# GEVCU-5.net
KiCad netlist of a schematic drawn in EAGLE
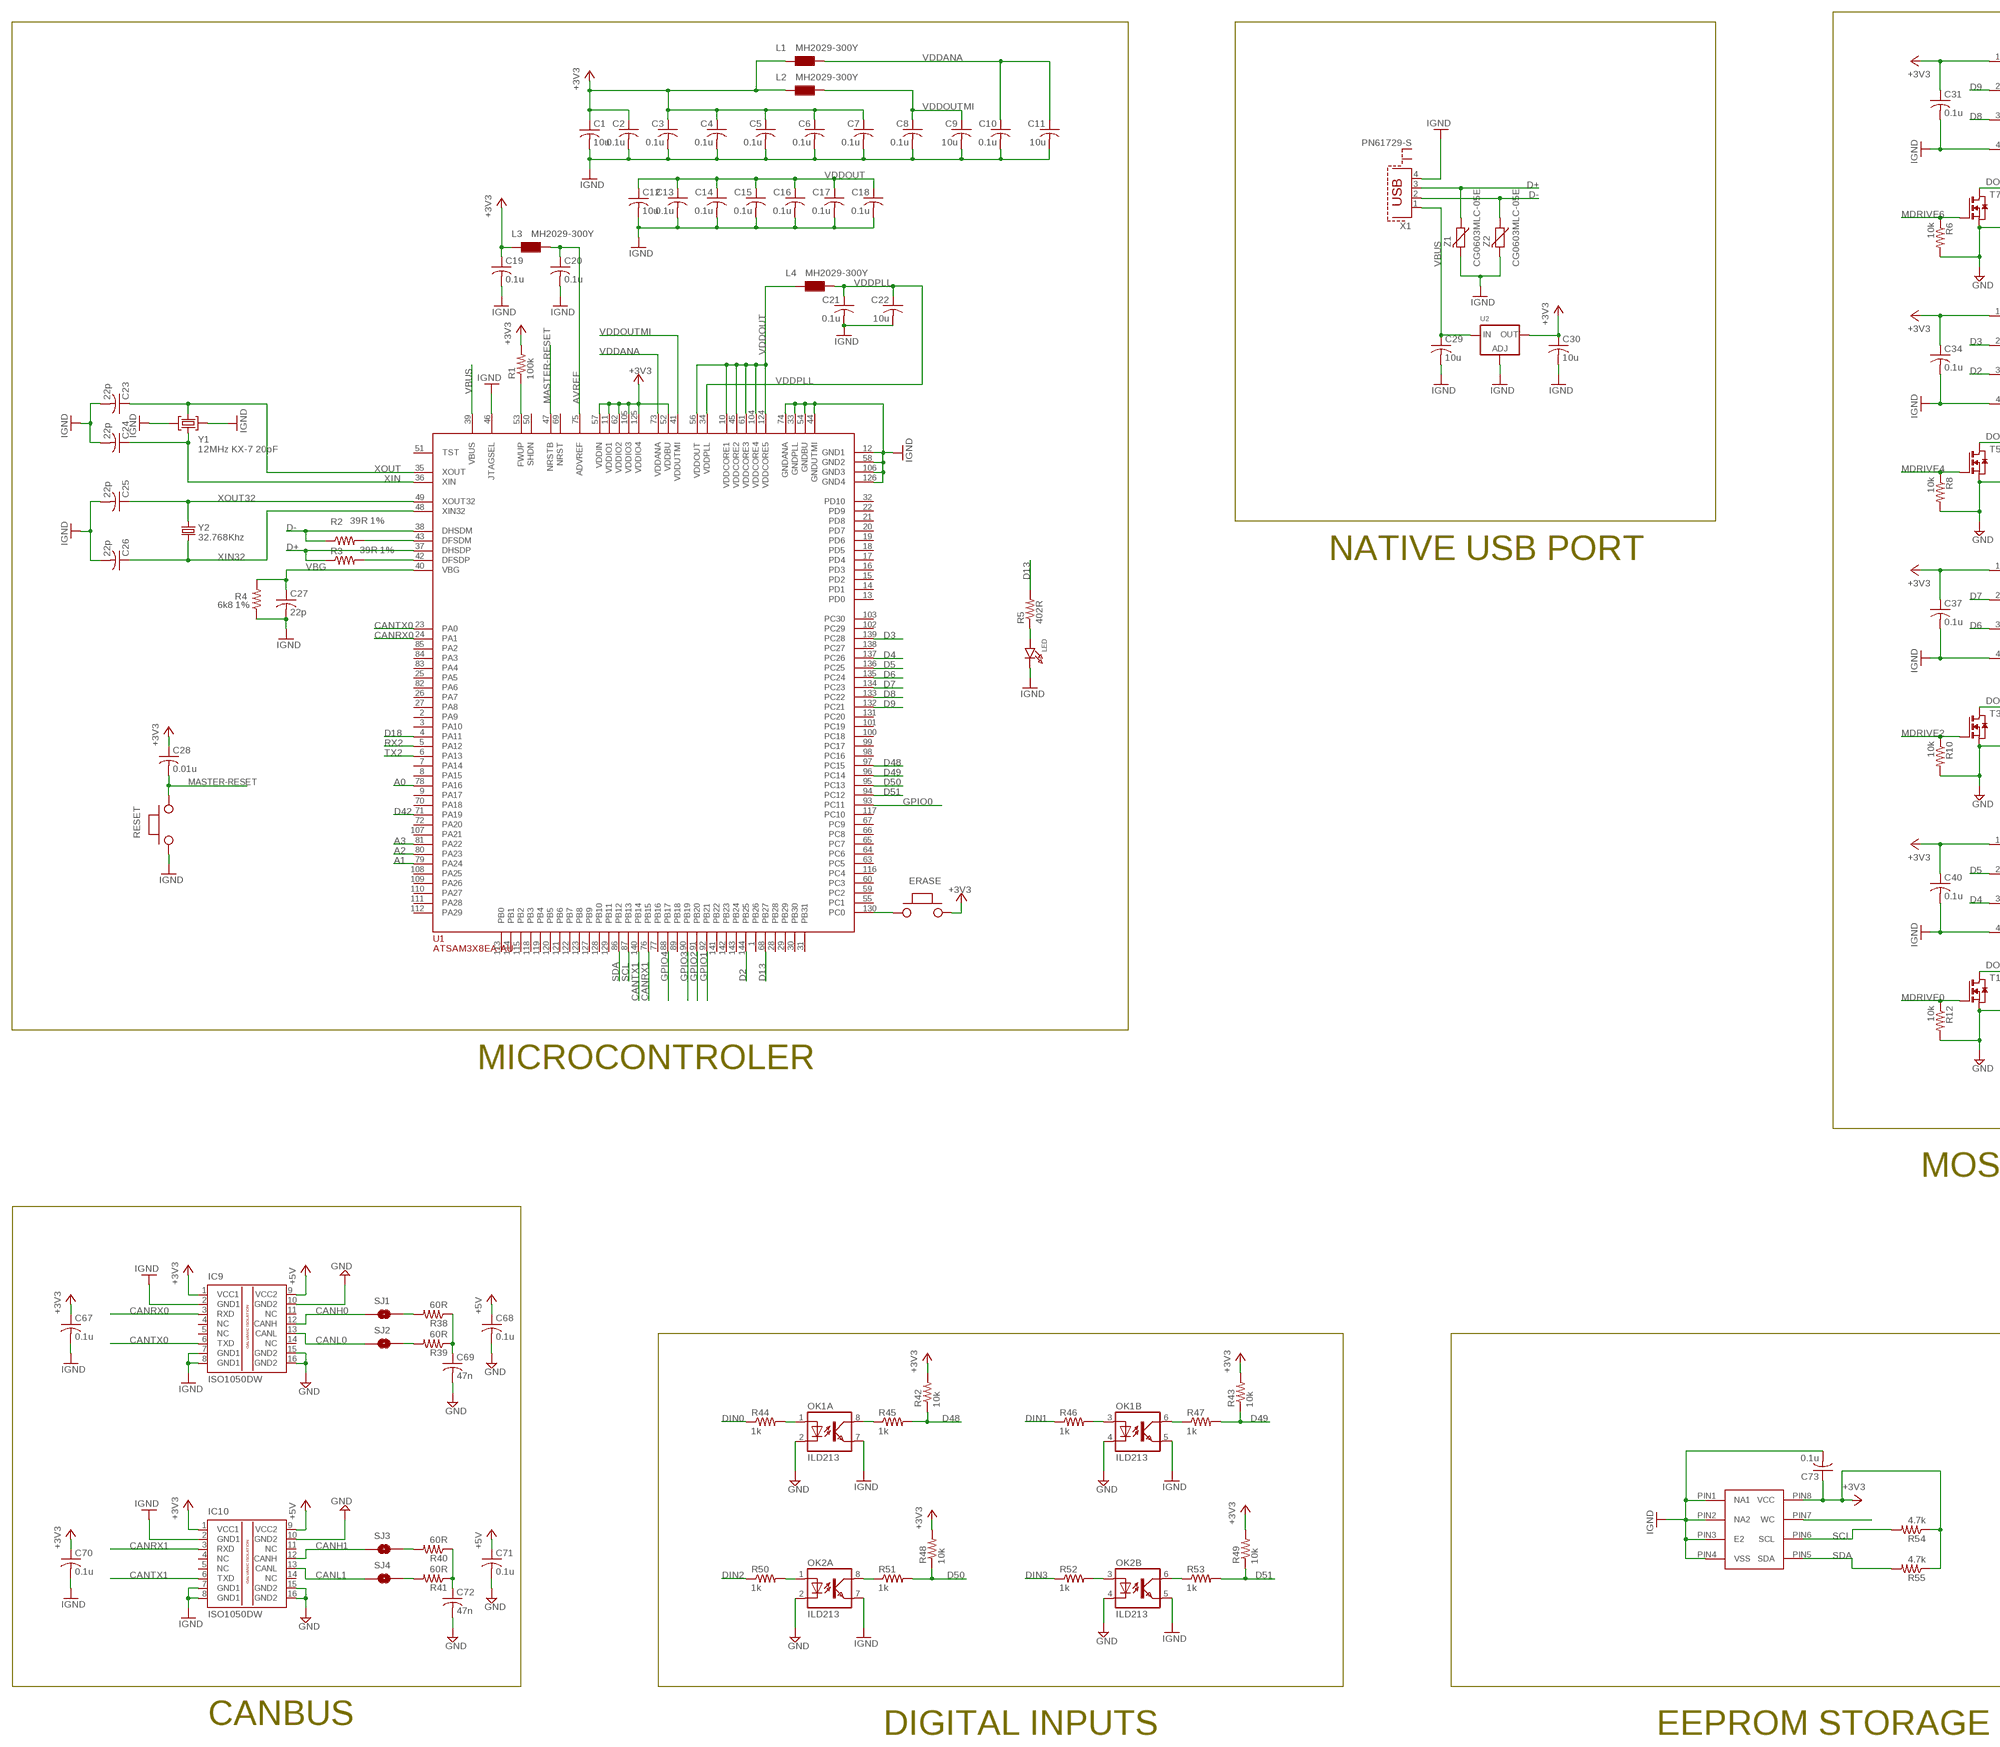
[diagram p0: schematic, sheet 1, part 1 of 2]
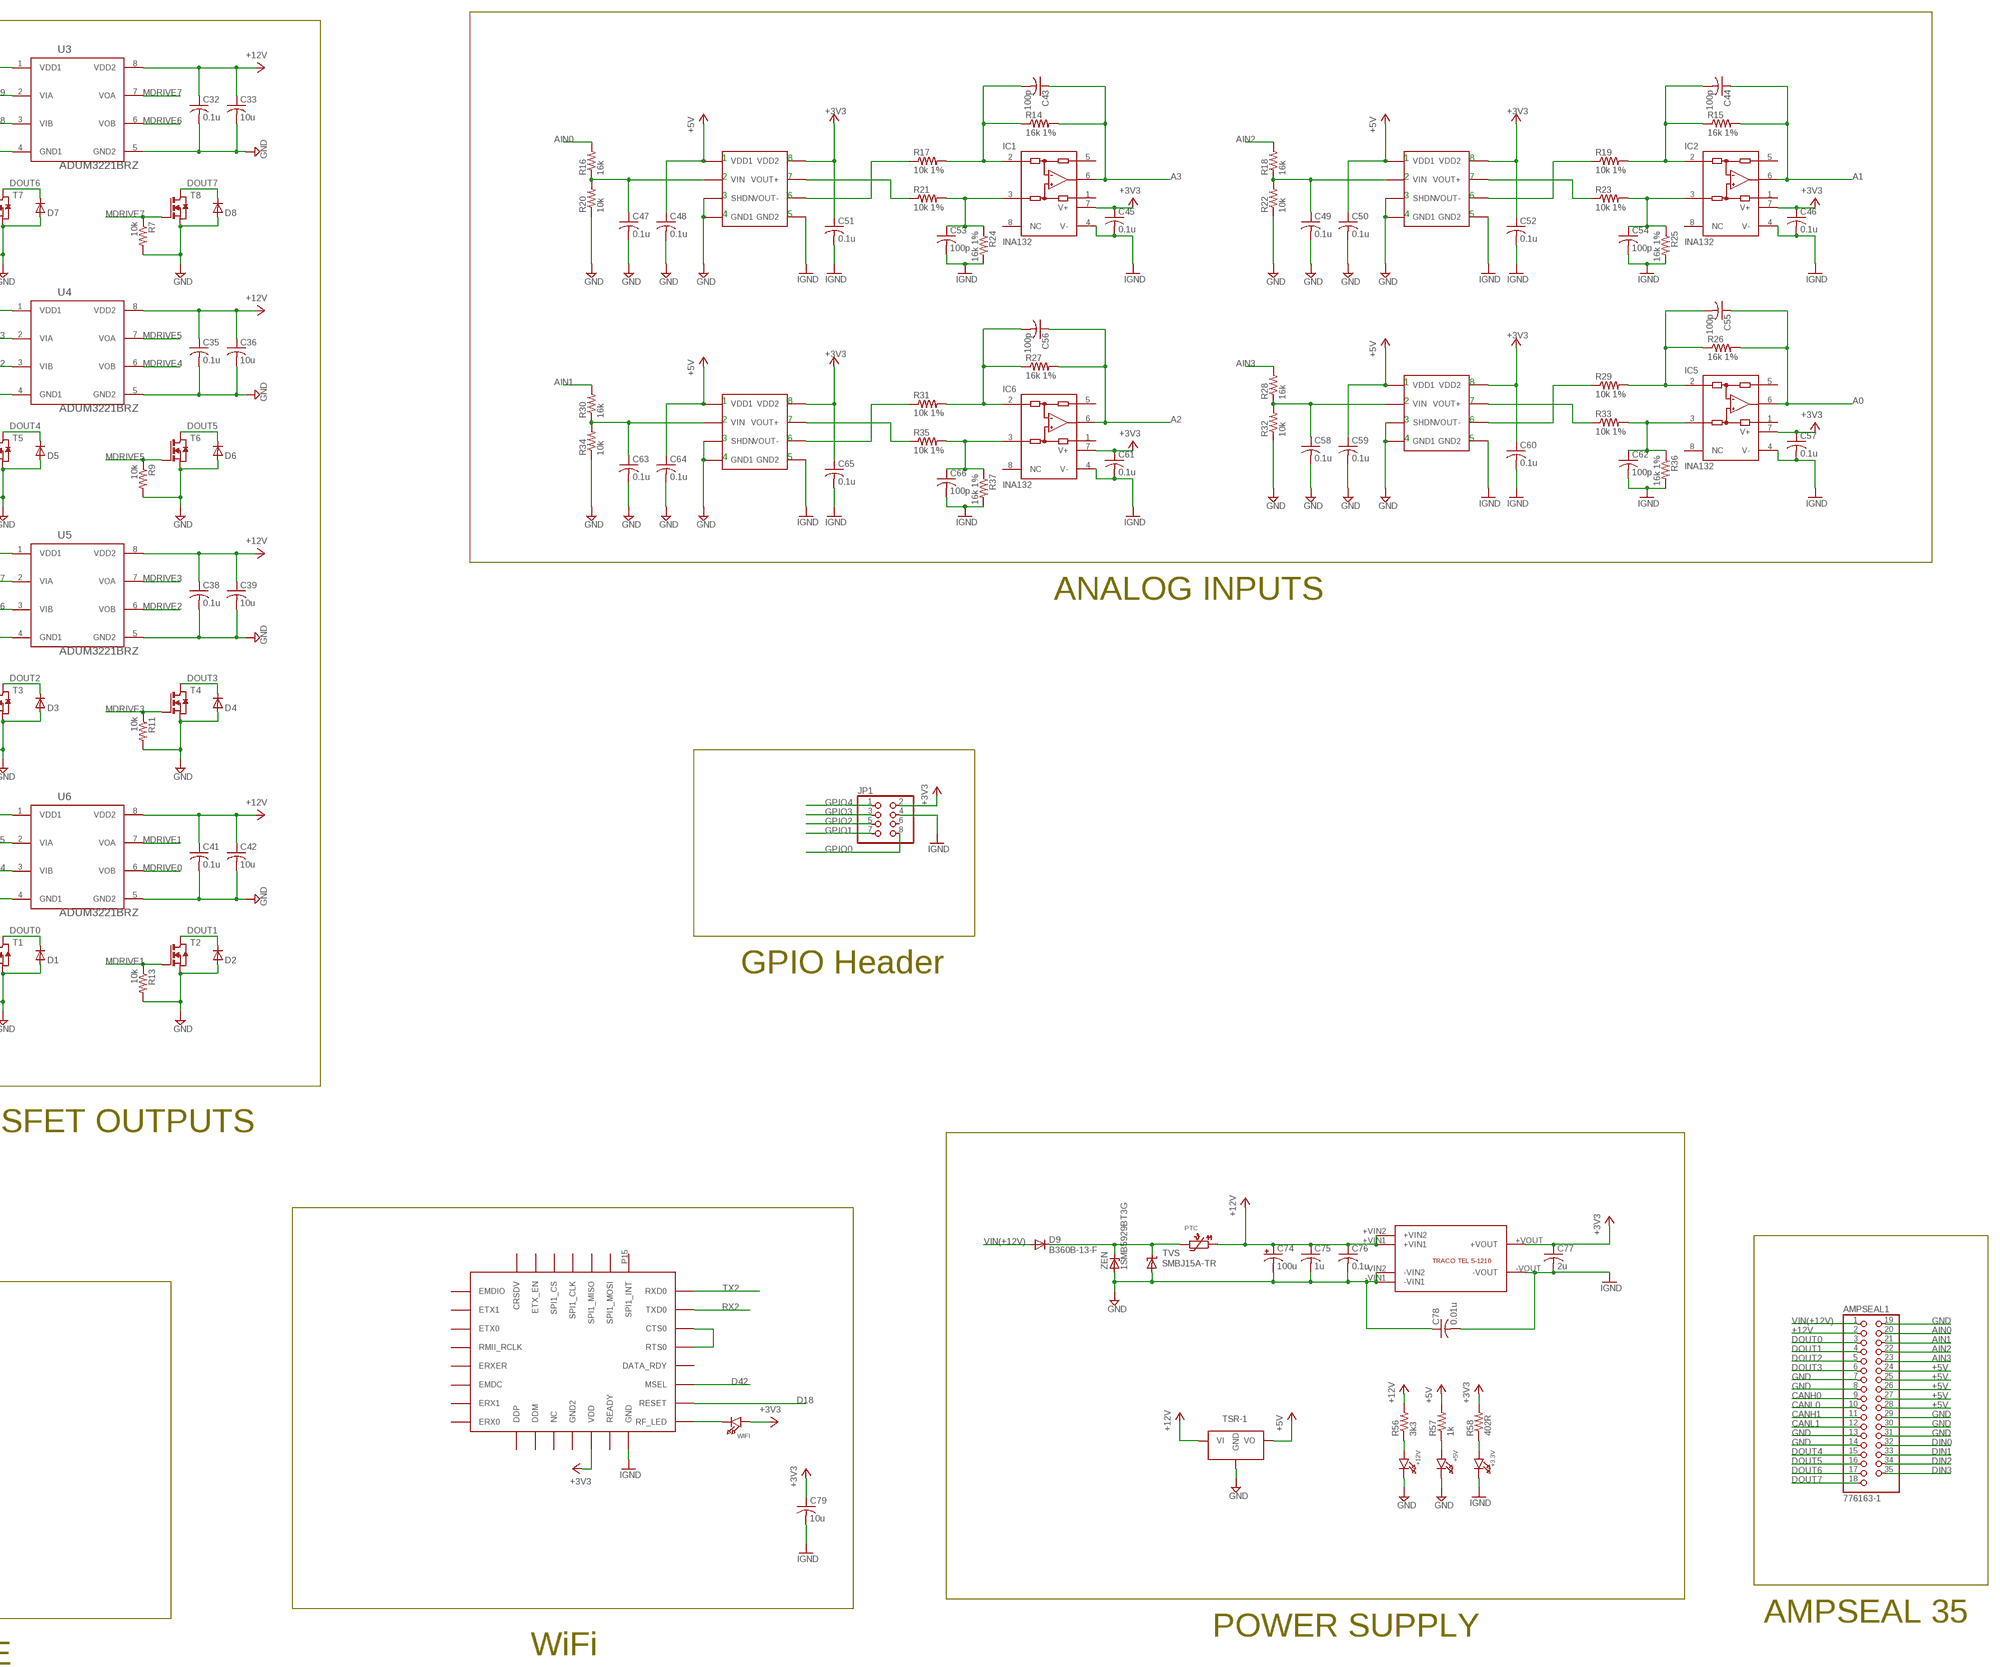
[diagram p1: schematic, sheet 1, part 2 of 2]

(export (version "E")
  (design (tool "Eeschema 10.0.6"))
  (components
    (comp (ref "+3.3V")
      (value "LED0805")
      (footprint "eagle-import:CHIPLED_0805")
      (libsource (lib "eagle-import") (part "LED0805"))
    )
    (comp (ref "+5V")
      (value "LED0805")
      (footprint "eagle-import:CHIPLED_0805")
      (libsource (lib "eagle-import") (part "LED0805"))
    )
    (comp (ref "+12V")
      (value "LED0805")
      (footprint "eagle-import:CHIPLED_0805")
      (libsource (lib "eagle-import") (part "LED0805"))
    )
    (comp (ref "AMPSEAL1")
      (value "776163-1")
      (footprint "eagle-import:AMPSEAL35")
      (libsource (lib "eagle-import") (part "AMPSEAL35"))
    )
    (comp (ref "C1")
      (value "10u")
      (footprint "eagle-import:C0805")
      (libsource (lib "eagle-import") (part "C-USC0805"))
    )
    (comp (ref "C2")
      (value "0.1u")
      (footprint "eagle-import:C0805")
      (libsource (lib "eagle-import") (part "C-USC0805"))
    )
    (comp (ref "C3")
      (value "0.1u")
      (footprint "eagle-import:C0805")
      (libsource (lib "eagle-import") (part "C-USC0805"))
    )
    (comp (ref "C4")
      (value "0.1u")
      (footprint "eagle-import:C0805")
      (libsource (lib "eagle-import") (part "C-USC0805"))
    )
    (comp (ref "C5")
      (value "0.1u")
      (footprint "eagle-import:C0805")
      (libsource (lib "eagle-import") (part "C-USC0805"))
    )
    (comp (ref "C6")
      (value "0.1u")
      (footprint "eagle-import:C0805")
      (libsource (lib "eagle-import") (part "C-USC0805"))
    )
    (comp (ref "C7")
      (value "0.1u")
      (footprint "eagle-import:C0805")
      (libsource (lib "eagle-import") (part "C-USC0805"))
    )
    (comp (ref "C8")
      (value "0.1u")
      (footprint "eagle-import:C0805")
      (libsource (lib "eagle-import") (part "C-USC0805"))
    )
    (comp (ref "C9")
      (value "10u")
      (footprint "eagle-import:C0805")
      (libsource (lib "eagle-import") (part "C-USC0805"))
    )
    (comp (ref "C10")
      (value "0.1u")
      (footprint "eagle-import:C0805")
      (libsource (lib "eagle-import") (part "C-USC0805"))
    )
    (comp (ref "C11")
      (value "10u")
      (footprint "eagle-import:C0805")
      (libsource (lib "eagle-import") (part "C-USC0805"))
    )
    (comp (ref "C12")
      (value "10u")
      (footprint "eagle-import:C0805")
      (libsource (lib "eagle-import") (part "C-USC0805"))
    )
    (comp (ref "C13")
      (value "0.1u")
      (footprint "eagle-import:C0805")
      (libsource (lib "eagle-import") (part "C-USC0805"))
    )
    (comp (ref "C14")
      (value "0.1u")
      (footprint "eagle-import:C0805")
      (libsource (lib "eagle-import") (part "C-USC0805"))
    )
    (comp (ref "C15")
      (value "0.1u")
      (footprint "eagle-import:C0805")
      (libsource (lib "eagle-import") (part "C-USC0805"))
    )
    (comp (ref "C16")
      (value "0.1u")
      (footprint "eagle-import:C0805")
      (libsource (lib "eagle-import") (part "C-USC0805"))
    )
    (comp (ref "C17")
      (value "0.1u")
      (footprint "eagle-import:C0805")
      (libsource (lib "eagle-import") (part "C-USC0805"))
    )
    (comp (ref "C18")
      (value "0.1u")
      (footprint "eagle-import:C0805")
      (libsource (lib "eagle-import") (part "C-USC0805"))
    )
    (comp (ref "C19")
      (value "0.1u")
      (footprint "eagle-import:C0805")
      (libsource (lib "eagle-import") (part "C-USC0805"))
    )
    (comp (ref "C20")
      (value "0.1u")
      (footprint "eagle-import:C0805")
      (libsource (lib "eagle-import") (part "C-USC0805"))
    )
    (comp (ref "C21")
      (value "0.1u")
      (footprint "eagle-import:C0805")
      (libsource (lib "eagle-import") (part "C-USC0805"))
    )
    (comp (ref "C22")
      (value "10u")
      (footprint "eagle-import:C0805")
      (libsource (lib "eagle-import") (part "C-USC0805"))
    )
    (comp (ref "C23")
      (value "22p")
      (footprint "eagle-import:C1206")
      (libsource (lib "eagle-import") (part "C-USC1206"))
    )
    (comp (ref "C24")
      (value "22p")
      (footprint "eagle-import:C1206")
      (libsource (lib "eagle-import") (part "C-USC1206"))
    )
    (comp (ref "C25")
      (value "22p")
      (footprint "eagle-import:C0805")
      (libsource (lib "eagle-import") (part "C-USC0805"))
    )
    (comp (ref "C26")
      (value "22p")
      (footprint "eagle-import:C0805")
      (libsource (lib "eagle-import") (part "C-USC0805"))
    )
    (comp (ref "C27")
      (value "22p")
      (footprint "eagle-import:C0805")
      (libsource (lib "eagle-import") (part "C-USC0805"))
    )
    (comp (ref "C28")
      (value "0.01u")
      (footprint "eagle-import:C0805")
      (libsource (lib "eagle-import") (part "C-USC0805"))
    )
    (comp (ref "C29")
      (value "10u")
      (footprint "eagle-import:C0805")
      (libsource (lib "eagle-import") (part "C-USC0805"))
    )
    (comp (ref "C30")
      (value "10u")
      (footprint "eagle-import:C0805")
      (libsource (lib "eagle-import") (part "C-USC0805"))
    )
    (comp (ref "C31")
      (value "0.1u")
      (footprint "eagle-import:C0805")
      (libsource (lib "eagle-import") (part "C-USC0805"))
    )
    (comp (ref "C32")
      (value "0.1u")
      (footprint "eagle-import:C0805")
      (libsource (lib "eagle-import") (part "C-USC0805"))
    )
    (comp (ref "C33")
      (value "10u")
      (footprint "eagle-import:C0805")
      (libsource (lib "eagle-import") (part "C-USC0805"))
    )
    (comp (ref "C34")
      (value "0.1u")
      (footprint "eagle-import:C0805")
      (libsource (lib "eagle-import") (part "C-USC0805"))
    )
    (comp (ref "C35")
      (value "0.1u")
      (footprint "eagle-import:C0805")
      (libsource (lib "eagle-import") (part "C-USC0805"))
    )
    (comp (ref "C36")
      (value "10u")
      (footprint "eagle-import:C0805")
      (libsource (lib "eagle-import") (part "C-USC0805"))
    )
    (comp (ref "C37")
      (value "0.1u")
      (footprint "eagle-import:C0805")
      (libsource (lib "eagle-import") (part "C-USC0805"))
    )
    (comp (ref "C38")
      (value "0.1u")
      (footprint "eagle-import:C0805")
      (libsource (lib "eagle-import") (part "C-USC0805"))
    )
    (comp (ref "C39")
      (value "10u")
      (footprint "eagle-import:C0805")
      (libsource (lib "eagle-import") (part "C-USC0805"))
    )
    (comp (ref "C40")
      (value "0.1u")
      (footprint "eagle-import:C0805")
      (libsource (lib "eagle-import") (part "C-USC0805"))
    )
    (comp (ref "C41")
      (value "0.1u")
      (footprint "eagle-import:C0805")
      (libsource (lib "eagle-import") (part "C-USC0805"))
    )
    (comp (ref "C42")
      (value "10u")
      (footprint "eagle-import:C0805")
      (libsource (lib "eagle-import") (part "C-USC0805"))
    )
    (comp (ref "C43")
      (value "100p")
      (footprint "eagle-import:C0805")
      (libsource (lib "eagle-import") (part "C-USC0805"))
    )
    (comp (ref "C44")
      (value "100p")
      (footprint "eagle-import:C0805")
      (libsource (lib "eagle-import") (part "C-USC0805"))
    )
    (comp (ref "C45")
      (value "0.1u")
      (footprint "eagle-import:C0805")
      (libsource (lib "eagle-import") (part "C-USC0805"))
    )
    (comp (ref "C46")
      (value "0.1u")
      (footprint "eagle-import:C0805")
      (libsource (lib "eagle-import") (part "C-USC0805"))
    )
    (comp (ref "C47")
      (value "0.1u")
      (footprint "eagle-import:C0805")
      (libsource (lib "eagle-import") (part "C-USC0805"))
    )
    (comp (ref "C48")
      (value "0.1u")
      (footprint "eagle-import:C1206")
      (libsource (lib "eagle-import") (part "C-USC1206"))
    )
    (comp (ref "C49")
      (value "0.1u")
      (footprint "eagle-import:C0805")
      (libsource (lib "eagle-import") (part "C-USC0805"))
    )
    (comp (ref "C50")
      (value "0.1u")
      (footprint "eagle-import:C1206")
      (libsource (lib "eagle-import") (part "C-USC1206"))
    )
    (comp (ref "C51")
      (value "0.1u")
      (footprint "eagle-import:C0805")
      (libsource (lib "eagle-import") (part "C-USC0805"))
    )
    (comp (ref "C52")
      (value "0.1u")
      (footprint "eagle-import:C0805")
      (libsource (lib "eagle-import") (part "C-USC0805"))
    )
    (comp (ref "C53")
      (value "100p")
      (footprint "eagle-import:C0805")
      (libsource (lib "eagle-import") (part "C-USC0805"))
    )
    (comp (ref "C54")
      (value "100p")
      (footprint "eagle-import:C0805")
      (libsource (lib "eagle-import") (part "C-USC0805"))
    )
    (comp (ref "C55")
      (value "100p")
      (footprint "eagle-import:C0805")
      (libsource (lib "eagle-import") (part "C-USC0805"))
    )
    (comp (ref "C56")
      (value "100p")
      (footprint "eagle-import:C0805")
      (libsource (lib "eagle-import") (part "C-USC0805"))
    )
    (comp (ref "C57")
      (value "0.1u")
      (footprint "eagle-import:C0805")
      (libsource (lib "eagle-import") (part "C-USC0805"))
    )
    (comp (ref "C58")
      (value "0.1u")
      (footprint "eagle-import:C0805")
      (libsource (lib "eagle-import") (part "C-USC0805"))
    )
    (comp (ref "C59")
      (value "0.1u")
      (footprint "eagle-import:C1206")
      (libsource (lib "eagle-import") (part "C-USC1206"))
    )
    (comp (ref "C60")
      (value "0.1u")
      (footprint "eagle-import:C0805")
      (libsource (lib "eagle-import") (part "C-USC0805"))
    )
    (comp (ref "C61")
      (value "0.1u")
      (footprint "eagle-import:C0805")
      (libsource (lib "eagle-import") (part "C-USC0805"))
    )
    (comp (ref "C62")
      (value "100p")
      (footprint "eagle-import:C0805")
      (libsource (lib "eagle-import") (part "C-USC0805"))
    )
    (comp (ref "C63")
      (value "0.1u")
      (footprint "eagle-import:C0805")
      (libsource (lib "eagle-import") (part "C-USC0805"))
    )
    (comp (ref "C64")
      (value "0.1u")
      (footprint "eagle-import:C1206")
      (libsource (lib "eagle-import") (part "C-USC1206"))
    )
    (comp (ref "C65")
      (value "0.1u")
      (footprint "eagle-import:C0805")
      (libsource (lib "eagle-import") (part "C-USC0805"))
    )
    (comp (ref "C66")
      (value "100p")
      (footprint "eagle-import:C0805")
      (libsource (lib "eagle-import") (part "C-USC0805"))
    )
    (comp (ref "C67")
      (value "0.1u")
      (footprint "eagle-import:C0805")
      (libsource (lib "eagle-import") (part "C-USC0805"))
    )
    (comp (ref "C68")
      (value "0.1u")
      (footprint "eagle-import:C0805")
      (libsource (lib "eagle-import") (part "C-USC0805"))
    )
    (comp (ref "C69")
      (value "47n")
      (footprint "eagle-import:C0805")
      (libsource (lib "eagle-import") (part "C-USC0805"))
    )
    (comp (ref "C70")
      (value "0.1u")
      (footprint "eagle-import:C0805")
      (libsource (lib "eagle-import") (part "C-USC0805"))
    )
    (comp (ref "C71")
      (value "0.1u")
      (footprint "eagle-import:C0805")
      (libsource (lib "eagle-import") (part "C-USC0805"))
    )
    (comp (ref "C72")
      (value "47n")
      (footprint "eagle-import:C0805")
      (libsource (lib "eagle-import") (part "C-USC0805"))
    )
    (comp (ref "C73")
      (value "0.1u")
      (footprint "eagle-import:C0805")
      (libsource (lib "eagle-import") (part "C-USC0805"))
    )
    (comp (ref "C74")
      (value "100u")
      (footprint "eagle-import:E2,5-6")
      (libsource (lib "eagle-import") (part "CPOL-USE2.5-6"))
    )
    (comp (ref "C75")
      (value "1u")
      (footprint "eagle-import:C0805")
      (libsource (lib "eagle-import") (part "C-USC0805"))
    )
    (comp (ref "C76")
      (value "0.1u")
      (footprint "eagle-import:C0805")
      (libsource (lib "eagle-import") (part "C-USC0805"))
    )
    (comp (ref "C77")
      (value "2u")
      (footprint "eagle-import:C0805")
      (libsource (lib "eagle-import") (part "C-USC0805"))
    )
    (comp (ref "C78")
      (value "0.01u")
      (footprint "eagle-import:C1812")
      (libsource (lib "eagle-import") (part "C-USC1812"))
    )
    (comp (ref "C79")
      (value "10u")
      (footprint "eagle-import:C0805")
      (libsource (lib "eagle-import") (part "C-USC0805"))
    )
    (comp (ref "D1")
      (value "MBR0520LT")
      (footprint "eagle-import:SOD123")
      (libsource (lib "eagle-import") (part "MBR0520LT"))
    )
    (comp (ref "D2")
      (value "MBR0520LT")
      (footprint "eagle-import:SOD123")
      (libsource (lib "eagle-import") (part "MBR0520LT"))
    )
    (comp (ref "D3")
      (value "MBR0520LT")
      (footprint "eagle-import:SOD123")
      (libsource (lib "eagle-import") (part "MBR0520LT"))
    )
    (comp (ref "D4")
      (value "MBR0520LT")
      (footprint "eagle-import:SOD123")
      (libsource (lib "eagle-import") (part "MBR0520LT"))
    )
    (comp (ref "D5")
      (value "MBR0520LT")
      (footprint "eagle-import:SOD123")
      (libsource (lib "eagle-import") (part "MBR0520LT"))
    )
    (comp (ref "D6")
      (value "MBR0520LT")
      (footprint "eagle-import:SOD123")
      (libsource (lib "eagle-import") (part "MBR0520LT"))
    )
    (comp (ref "D7")
      (value "MBR0520LT")
      (footprint "eagle-import:SOD123")
      (libsource (lib "eagle-import") (part "MBR0520LT"))
    )
    (comp (ref "D8")
      (value "MBR0520LT")
      (footprint "eagle-import:SOD123")
      (libsource (lib "eagle-import") (part "MBR0520LT"))
    )
    (comp (ref "D9")
      (value "B360B-13-F")
      (footprint "eagle-import:SMB")
      (libsource (lib "eagle-import") (part "DIODE-SMB"))
    )
    (comp (ref "ERASE")
      (value "PUCHBUTTON")
      (footprint "eagle-import:PUCHBUTTON")
      (libsource (lib "eagle-import") (part "PUCHBUTTON"))
    )
    (comp (ref "IC1")
      (value "INA132")
      (footprint "eagle-import:SO08")
      (fields (field (name "MF") "TEXAS INSTRUMENTS") (field (name "MPN") "INA105KU"))
      (libsource (lib "eagle-import") (part "INA105U"))
    )
    (comp (ref "IC2")
      (value "INA132")
      (footprint "eagle-import:SO08")
      (fields (field (name "MF") "TEXAS INSTRUMENTS") (field (name "MPN") "INA105KU"))
      (libsource (lib "eagle-import") (part "INA105U"))
    )
    (comp (ref "IC3")
      (value "CK_CUSTOM_ACPL-C87A-000E")
      (footprint "eagle-import:CK_CUSTOM_SO8-WIDE")
      (libsource (lib "eagle-import") (part "CK_CUSTOM_ACPL-C87A-000E"))
    )
    (comp (ref "IC4")
      (value "CK_CUSTOM_ACPL-C87A-000E")
      (footprint "eagle-import:CK_CUSTOM_SO8-WIDE")
      (libsource (lib "eagle-import") (part "CK_CUSTOM_ACPL-C87A-000E"))
    )
    (comp (ref "IC5")
      (value "INA132")
      (footprint "eagle-import:SO08")
      (fields (field (name "MF") "TEXAS INSTRUMENTS") (field (name "MPN") "INA105KU"))
      (libsource (lib "eagle-import") (part "INA105U"))
    )
    (comp (ref "IC6")
      (value "INA132")
      (footprint "eagle-import:SO08")
      (fields (field (name "MF") "TEXAS INSTRUMENTS") (field (name "MPN") "INA105KU"))
      (libsource (lib "eagle-import") (part "INA105U"))
    )
    (comp (ref "IC7")
      (value "CK_CUSTOM_ACPL-C87A-000E")
      (footprint "eagle-import:CK_CUSTOM_SO8-WIDE")
      (libsource (lib "eagle-import") (part "CK_CUSTOM_ACPL-C87A-000E"))
    )
    (comp (ref "IC8")
      (value "CK_CUSTOM_ACPL-C87A-000E")
      (footprint "eagle-import:CK_CUSTOM_SO8-WIDE")
      (libsource (lib "eagle-import") (part "CK_CUSTOM_ACPL-C87A-000E"))
    )
    (comp (ref "IC9")
      (value "ISO1050DW")
      (footprint "eagle-import:DUB-R-PDSO-G8")
      (libsource (lib "eagle-import") (part "ISO1050DUB"))
    )
    (comp (ref "IC10")
      (value "ISO1050DW")
      (footprint "eagle-import:DUB-R-PDSO-G8")
      (libsource (lib "eagle-import") (part "ISO1050DUB"))
    )
    (comp (ref "JP1")
      (value "PINHD-2X4")
      (footprint "eagle-import:2X04")
      (libsource (lib "eagle-import") (part "PINHD-2X4"))
    )
    (comp (ref "L1")
      (value "MH2029-300Y")
      (footprint "eagle-import:0805")
      (libsource (lib "eagle-import") (part "WE-CBF_0805"))
    )
    (comp (ref "L2")
      (value "MH2029-300Y")
      (footprint "eagle-import:0805")
      (libsource (lib "eagle-import") (part "WE-CBF_0805"))
    )
    (comp (ref "L3")
      (value "MH2029-300Y")
      (footprint "eagle-import:0805")
      (libsource (lib "eagle-import") (part "WE-CBF_0805"))
    )
    (comp (ref "L4")
      (value "MH2029-300Y")
      (footprint "eagle-import:0805")
      (libsource (lib "eagle-import") (part "WE-CBF_0805"))
    )
    (comp (ref "LED")
      (value "LED0805")
      (footprint "eagle-import:CHIPLED_0805")
      (libsource (lib "eagle-import") (part "LED0805"))
    )
    (comp (ref "OK1")
      (value "ILD213")
      (footprint "eagle-import:SOIC08")
      (fields (field (name "MF") "VISHAY/TELEFUNKEN") (field (name "MPN") "ILD213T"))
      (libsource (lib "eagle-import") (part "ILD213"))
    )
    (comp (ref "OK2")
      (value "ILD213")
      (footprint "eagle-import:SOIC08")
      (fields (field (name "MF") "VISHAY/TELEFUNKEN") (field (name "MPN") "ILD213T"))
      (libsource (lib "eagle-import") (part "ILD213"))
    )
    (comp (ref "PTC")
      (value "PTC1812")
      (footprint "eagle-import:PTC1812")
      (libsource (lib "eagle-import") (part "PTC1812"))
    )
    (comp (ref "R1")
      (value "100k")
      (footprint "eagle-import:R0805")
      (libsource (lib "eagle-import") (part "R-US_R0805"))
    )
    (comp (ref "R2")
      (value "39R 1%")
      (footprint "eagle-import:R0805")
      (libsource (lib "eagle-import") (part "R-US_R0805"))
    )
    (comp (ref "R3")
      (value "39R 1%")
      (footprint "eagle-import:R0805")
      (libsource (lib "eagle-import") (part "R-US_R0805"))
    )
    (comp (ref "R4")
      (value "6k8 1%")
      (footprint "eagle-import:R0805")
      (libsource (lib "eagle-import") (part "R-US_R0805"))
    )
    (comp (ref "R5")
      (value "402R")
      (footprint "eagle-import:R0805")
      (libsource (lib "eagle-import") (part "R-US_R0805"))
    )
    (comp (ref "R6")
      (value "10k")
      (footprint "eagle-import:R0805")
      (libsource (lib "eagle-import") (part "R-US_R0805"))
    )
    (comp (ref "R7")
      (value "10k")
      (footprint "eagle-import:R0805")
      (libsource (lib "eagle-import") (part "R-US_R0805"))
    )
    (comp (ref "R8")
      (value "10k")
      (footprint "eagle-import:R0805")
      (libsource (lib "eagle-import") (part "R-US_R0805"))
    )
    (comp (ref "R9")
      (value "10k")
      (footprint "eagle-import:R0805")
      (libsource (lib "eagle-import") (part "R-US_R0805"))
    )
    (comp (ref "R10")
      (value "10k")
      (footprint "eagle-import:R0805")
      (libsource (lib "eagle-import") (part "R-US_R0805"))
    )
    (comp (ref "R11")
      (value "10k")
      (footprint "eagle-import:R0805")
      (libsource (lib "eagle-import") (part "R-US_R0805"))
    )
    (comp (ref "R12")
      (value "10k")
      (footprint "eagle-import:R0805")
      (libsource (lib "eagle-import") (part "R-US_R0805"))
    )
    (comp (ref "R13")
      (value "10k")
      (footprint "eagle-import:R0805")
      (libsource (lib "eagle-import") (part "R-US_R0805"))
    )
    (comp (ref "R14")
      (value "16k 1%")
      (footprint "eagle-import:R0805")
      (libsource (lib "eagle-import") (part "R-US_R0805"))
    )
    (comp (ref "R15")
      (value "16k 1%")
      (footprint "eagle-import:R0805")
      (libsource (lib "eagle-import") (part "R-US_R0805"))
    )
    (comp (ref "R16")
      (value "16k")
      (footprint "eagle-import:R0805")
      (libsource (lib "eagle-import") (part "R-US_R0805"))
    )
    (comp (ref "R17")
      (value "10k 1%")
      (footprint "eagle-import:R0805")
      (libsource (lib "eagle-import") (part "R-US_R0805"))
    )
    (comp (ref "R18")
      (value "16k")
      (footprint "eagle-import:R0805")
      (libsource (lib "eagle-import") (part "R-US_R0805"))
    )
    (comp (ref "R19")
      (value "10k 1%")
      (footprint "eagle-import:R0805")
      (libsource (lib "eagle-import") (part "R-US_R0805"))
    )
    (comp (ref "R20")
      (value "10k")
      (footprint "eagle-import:R0805")
      (libsource (lib "eagle-import") (part "R-US_R0805"))
    )
    (comp (ref "R21")
      (value "10k 1%")
      (footprint "eagle-import:R0805")
      (libsource (lib "eagle-import") (part "R-US_R0805"))
    )
    (comp (ref "R22")
      (value "10k")
      (footprint "eagle-import:R0805")
      (libsource (lib "eagle-import") (part "R-US_R0805"))
    )
    (comp (ref "R23")
      (value "10k 1%")
      (footprint "eagle-import:R0805")
      (libsource (lib "eagle-import") (part "R-US_R0805"))
    )
    (comp (ref "R24")
      (value "16k 1%")
      (footprint "eagle-import:R0805")
      (libsource (lib "eagle-import") (part "R-US_R0805"))
    )
    (comp (ref "R25")
      (value "16k 1%")
      (footprint "eagle-import:R0805")
      (libsource (lib "eagle-import") (part "R-US_R0805"))
    )
    (comp (ref "R26")
      (value "16k 1%")
      (footprint "eagle-import:R0805")
      (libsource (lib "eagle-import") (part "R-US_R0805"))
    )
    (comp (ref "R27")
      (value "16k 1%")
      (footprint "eagle-import:R0805")
      (libsource (lib "eagle-import") (part "R-US_R0805"))
    )
    (comp (ref "R28")
      (value "16k")
      (footprint "eagle-import:R0805")
      (libsource (lib "eagle-import") (part "R-US_R0805"))
    )
    (comp (ref "R29")
      (value "10k 1%")
      (footprint "eagle-import:R0805")
      (libsource (lib "eagle-import") (part "R-US_R0805"))
    )
    (comp (ref "R30")
      (value "16k")
      (footprint "eagle-import:R0805")
      (libsource (lib "eagle-import") (part "R-US_R0805"))
    )
    (comp (ref "R31")
      (value "10k 1%")
      (footprint "eagle-import:R0805")
      (libsource (lib "eagle-import") (part "R-US_R0805"))
    )
    (comp (ref "R32")
      (value "10k")
      (footprint "eagle-import:R0805")
      (libsource (lib "eagle-import") (part "R-US_R0805"))
    )
    (comp (ref "R33")
      (value "10k 1%")
      (footprint "eagle-import:R0805")
      (libsource (lib "eagle-import") (part "R-US_R0805"))
    )
    (comp (ref "R34")
      (value "10k")
      (footprint "eagle-import:R0805")
      (libsource (lib "eagle-import") (part "R-US_R0805"))
    )
    (comp (ref "R35")
      (value "10k 1%")
      (footprint "eagle-import:R0805")
      (libsource (lib "eagle-import") (part "R-US_R0805"))
    )
    (comp (ref "R36")
      (value "16k 1%")
      (footprint "eagle-import:R0805")
      (libsource (lib "eagle-import") (part "R-US_R0805"))
    )
    (comp (ref "R37")
      (value "16k 1%")
      (footprint "eagle-import:R0805")
      (libsource (lib "eagle-import") (part "R-US_R0805"))
    )
    (comp (ref "R38")
      (value "60R")
      (footprint "eagle-import:R0805")
      (libsource (lib "eagle-import") (part "R-US_R0805"))
    )
    (comp (ref "R39")
      (value "60R")
      (footprint "eagle-import:R0805")
      (libsource (lib "eagle-import") (part "R-US_R0805"))
    )
    (comp (ref "R40")
      (value "60R")
      (footprint "eagle-import:R0805")
      (libsource (lib "eagle-import") (part "R-US_R0805"))
    )
    (comp (ref "R41")
      (value "60R")
      (footprint "eagle-import:R0805")
      (libsource (lib "eagle-import") (part "R-US_R0805"))
    )
    (comp (ref "R42")
      (value "10k")
      (footprint "eagle-import:R0805")
      (libsource (lib "eagle-import") (part "R-US_R0805"))
    )
    (comp (ref "R43")
      (value "10k")
      (footprint "eagle-import:R0805")
      (libsource (lib "eagle-import") (part "R-US_R0805"))
    )
    (comp (ref "R44")
      (value "1k")
      (footprint "eagle-import:R0805")
      (libsource (lib "eagle-import") (part "R-US_R0805"))
    )
    (comp (ref "R45")
      (value "1k")
      (footprint "eagle-import:R0805")
      (libsource (lib "eagle-import") (part "R-US_R0805"))
    )
    (comp (ref "R46")
      (value "1k")
      (footprint "eagle-import:R0805")
      (libsource (lib "eagle-import") (part "R-US_R0805"))
    )
    (comp (ref "R47")
      (value "1k")
      (footprint "eagle-import:R0805")
      (libsource (lib "eagle-import") (part "R-US_R0805"))
    )
    (comp (ref "R48")
      (value "10k")
      (footprint "eagle-import:R0805")
      (libsource (lib "eagle-import") (part "R-US_R0805"))
    )
    (comp (ref "R49")
      (value "10k")
      (footprint "eagle-import:R0805")
      (libsource (lib "eagle-import") (part "R-US_R0805"))
    )
    (comp (ref "R50")
      (value "1k")
      (footprint "eagle-import:R0805")
      (libsource (lib "eagle-import") (part "R-US_R0805"))
    )
    (comp (ref "R51")
      (value "1k")
      (footprint "eagle-import:R0805")
      (libsource (lib "eagle-import") (part "R-US_R0805"))
    )
    (comp (ref "R52")
      (value "1k")
      (footprint "eagle-import:R0805")
      (libsource (lib "eagle-import") (part "R-US_R0805"))
    )
    (comp (ref "R53")
      (value "1k")
      (footprint "eagle-import:R0805")
      (libsource (lib "eagle-import") (part "R-US_R0805"))
    )
    (comp (ref "R54")
      (value "4.7k")
      (footprint "eagle-import:R0805")
      (libsource (lib "eagle-import") (part "R-US_R0805"))
    )
    (comp (ref "R55")
      (value "4.7k")
      (footprint "eagle-import:R0805")
      (libsource (lib "eagle-import") (part "R-US_R0805"))
    )
    (comp (ref "R56")
      (value "3k3")
      (footprint "eagle-import:R0805")
      (libsource (lib "eagle-import") (part "R-US_R0805"))
    )
    (comp (ref "R57")
      (value "1k")
      (footprint "eagle-import:R0805")
      (libsource (lib "eagle-import") (part "R-US_R0805"))
    )
    (comp (ref "R58")
      (value "402R")
      (footprint "eagle-import:R0805")
      (libsource (lib "eagle-import") (part "R-US_R0805"))
    )
    (comp (ref "RESET")
      (value "PUCHBUTTON")
      (footprint "eagle-import:PUCHBUTTON")
      (libsource (lib "eagle-import") (part "PUCHBUTTON"))
    )
    (comp (ref "SJ1")
      (value "SOLDERJUMPERNO")
      (footprint "eagle-import:SJ_2S-NO")
      (libsource (lib "eagle-import") (part "SOLDERJUMPERNO"))
    )
    (comp (ref "SJ2")
      (value "SOLDERJUMPERNO")
      (footprint "eagle-import:SJ_2S-NO")
      (libsource (lib "eagle-import") (part "SOLDERJUMPERNO"))
    )
    (comp (ref "SJ3")
      (value "SOLDERJUMPERNO")
      (footprint "eagle-import:SJ_2S-NO")
      (libsource (lib "eagle-import") (part "SOLDERJUMPERNO"))
    )
    (comp (ref "SJ4")
      (value "SOLDERJUMPERNO")
      (footprint "eagle-import:SJ_2S-NO")
      (libsource (lib "eagle-import") (part "SOLDERJUMPERNO"))
    )
    (comp (ref "T1")
      (value "NMOSSOT223")
      (footprint "eagle-import:SOT223")
      (libsource (lib "eagle-import") (part "NMOSSOT223"))
    )
    (comp (ref "T2")
      (value "NMOSSOT223")
      (footprint "eagle-import:SOT223")
      (libsource (lib "eagle-import") (part "NMOSSOT223"))
    )
    (comp (ref "T3")
      (value "NMOSSOT223")
      (footprint "eagle-import:SOT223")
      (libsource (lib "eagle-import") (part "NMOSSOT223"))
    )
    (comp (ref "T4")
      (value "NMOSSOT223")
      (footprint "eagle-import:SOT223")
      (libsource (lib "eagle-import") (part "NMOSSOT223"))
    )
    (comp (ref "T5")
      (value "NMOSSOT223")
      (footprint "eagle-import:SOT223")
      (libsource (lib "eagle-import") (part "NMOSSOT223"))
    )
    (comp (ref "T6")
      (value "NMOSSOT223")
      (footprint "eagle-import:SOT223")
      (libsource (lib "eagle-import") (part "NMOSSOT223"))
    )
    (comp (ref "T7")
      (value "NMOSSOT223")
      (footprint "eagle-import:SOT223")
      (libsource (lib "eagle-import") (part "NMOSSOT223"))
    )
    (comp (ref "T8")
      (value "NMOSSOT223")
      (footprint "eagle-import:SOT223")
      (libsource (lib "eagle-import") (part "NMOSSOT223"))
    )
    (comp (ref "TVS")
      (value "SMBJ15A-TR")
      (footprint "eagle-import:SMBJ")
      (libsource (lib "eagle-import") (part "SUPPRESSOR-SMBJ"))
    )
    (comp (ref "U$1")
      (value "NANOREACH")
      (footprint "eagle-import:NANOREACH")
      (libsource (lib "eagle-import") (part "NANOREACH"))
    )
    (comp (ref "U1")
      (value "ATSAM3X8EA-AU")
      (footprint "eagle-import:LQFP144")
      (libsource (lib "eagle-import") (part "ATSAM3X/AAU"))
    )
    (comp (ref "U2")
      (value "LM1117SOT223-WAVE")
      (footprint "eagle-import:SOT223-W")
      (libsource (lib "eagle-import") (part "LM1117SOT223-WAVE"))
    )
    (comp (ref "U3")
      (value "ADUM3221BRZ")
      (footprint "eagle-import:SOIC127P600X175-8N")
      (libsource (lib "eagle-import") (part "ADUM3221BRZ"))
    )
    (comp (ref "U4")
      (value "ADUM3221BRZ")
      (footprint "eagle-import:SOIC127P600X175-8N")
      (libsource (lib "eagle-import") (part "ADUM3221BRZ"))
    )
    (comp (ref "U5")
      (value "ADUM3221BRZ")
      (footprint "eagle-import:SOIC127P600X175-8N")
      (libsource (lib "eagle-import") (part "ADUM3221BRZ"))
    )
    (comp (ref "U6")
      (value "ADUM3221BRZ")
      (footprint "eagle-import:SOIC127P600X175-8N")
      (libsource (lib "eagle-import") (part "ADUM3221BRZ"))
    )
    (comp (ref "U7")
      (value "CK_CUSTOM_M24M02-DRMN6TP")
      (footprint "eagle-import:CK_CUSTOM_SOIC8")
      (libsource (lib "eagle-import") (part "CK_CUSTOM_M24M02-DRMN6TP"))
    )
    (comp (ref "U8")
      (value "TRACO")
      (footprint "eagle-import:TRACO")
      (libsource (lib "eagle-import") (part "TRACO"))
    )
    (comp (ref "U9")
      (value "TSR-1")
      (footprint "eagle-import:TSR-1")
      (libsource (lib "eagle-import") (part "TSR-1"))
    )
    (comp (ref "WIFI")
      (value "LED0805")
      (footprint "eagle-import:CHIPLED_0805")
      (libsource (lib "eagle-import") (part "LED0805"))
    )
    (comp (ref "X1")
      (value "PN61729-S")
      (footprint "eagle-import:PN61729-S")
      (libsource (lib "eagle-import") (part "PN61729-S"))
    )
    (comp (ref "Y1")
      (value "12MHz KX-7 20pF")
      (footprint "eagle-import:CRYSTAL-3.2-2.5")
      (libsource (lib "eagle-import") (part "CRYSTAL-3.2-2.5"))
    )
    (comp (ref "Y2")
      (value "32.768Khz")
      (footprint "eagle-import:ARDUINO_WIFI_SHIELD_V018_TG_RESONATOR_EPSON_FC_145")
      (libsource (lib "eagle-import") (part "ARDUINO_WIFI_SHIELD_V018_TG_RESONATOR_EPSON_FC_145"))
    )
    (comp (ref "Z1")
      (value "CG0603MLC-05E")
      (footprint "eagle-import:CT_CN0603")
      (libsource (lib "eagle-import") (part "VARISTORCN0603"))
    )
    (comp (ref "Z2")
      (value "CG0603MLC-05E")
      (footprint "eagle-import:CT_CN0603")
      (libsource (lib "eagle-import") (part "VARISTORCN0603"))
    )
    (comp (ref "ZEN")
      (value "1SMB5929BT3G")
      (footprint "eagle-import:SMB")
      (libsource (lib "eagle-import") (part "ZENER-DIODESMB"))
    )
  )
  (nets
    (net (code "1") (name "+3V3") (class "Default")
      (node (ref "C1") (pin "1") (pinfunction "1_1") (pintype "passive"))
      (node (ref "C19") (pin "1") (pinfunction "1_1") (pintype "passive"))
      (node (ref "C2") (pin "1") (pinfunction "1_1") (pintype "passive"))
      (node (ref "C28") (pin "1") (pinfunction "1_1") (pintype "passive"))
      (node (ref "C3") (pin "1") (pinfunction "1_1") (pintype "passive"))
      (node (ref "C30") (pin "1") (pinfunction "1_1") (pintype "passive"))
      (node (ref "C31") (pin "1") (pinfunction "1_1") (pintype "passive"))
      (node (ref "C34") (pin "1") (pinfunction "1_1") (pintype "passive"))
      (node (ref "C37") (pin "1") (pinfunction "1_1") (pintype "passive"))
      (node (ref "C4") (pin "1") (pinfunction "1_1") (pintype "passive"))
      (node (ref "C40") (pin "1") (pinfunction "1_1") (pintype "passive"))
      (node (ref "C45") (pin "1") (pinfunction "1_1") (pintype "passive"))
      (node (ref "C46") (pin "1") (pinfunction "1_1") (pintype "passive"))
      (node (ref "C5") (pin "1") (pinfunction "1_1") (pintype "passive"))
      (node (ref "C51") (pin "1") (pinfunction "1_1") (pintype "passive"))
      (node (ref "C52") (pin "1") (pinfunction "1_1") (pintype "passive"))
      (node (ref "C57") (pin "1") (pinfunction "1_1") (pintype "passive"))
      (node (ref "C6") (pin "1") (pinfunction "1_1") (pintype "passive"))
      (node (ref "C60") (pin "1") (pinfunction "1_1") (pintype "passive"))
      (node (ref "C61") (pin "1") (pinfunction "1_1") (pintype "passive"))
      (node (ref "C65") (pin "1") (pinfunction "1_1") (pintype "passive"))
      (node (ref "C67") (pin "1") (pinfunction "1_1") (pintype "passive"))
      (node (ref "C7") (pin "1") (pinfunction "1_1") (pintype "passive"))
      (node (ref "C70") (pin "1") (pinfunction "1_1") (pintype "passive"))
      (node (ref "C73") (pin "1") (pinfunction "1_1") (pintype "passive"))
      (node (ref "C77") (pin "1") (pinfunction "1_1") (pintype "passive"))
      (node (ref "C79") (pin "1") (pinfunction "1_1") (pintype "passive"))
      (node (ref "ERASE") (pin "P$2") (pinfunction "P$5_P$2") (pintype "bidirectional"))
      (node (ref "IC1") (pin "7") (pinfunction "V+_7") (pintype "power_in"))
      (node (ref "IC10") (pin "1") (pinfunction "VCC1_1") (pintype "input"))
      (node (ref "IC2") (pin "7") (pinfunction "V+_7") (pintype "power_in"))
      (node (ref "IC3") (pin "8") (pinfunction "VDD2_8") (pintype "bidirectional"))
      (node (ref "IC4") (pin "8") (pinfunction "VDD2_8") (pintype "bidirectional"))
      (node (ref "IC5") (pin "7") (pinfunction "V+_7") (pintype "power_in"))
      (node (ref "IC6") (pin "7") (pinfunction "V+_7") (pintype "power_in"))
      (node (ref "IC7") (pin "8") (pinfunction "VDD2_8") (pintype "bidirectional"))
      (node (ref "IC8") (pin "8") (pinfunction "VDD2_8") (pintype "bidirectional"))
      (node (ref "IC9") (pin "1") (pinfunction "VCC1_1") (pintype "input"))
      (node (ref "JP1") (pin "2") (pinfunction "2_2") (pintype "passive"))
      (node (ref "L1") (pin "1") (pinfunction "1_1") (pintype "passive"))
      (node (ref "L2") (pin "1") (pinfunction "1_1") (pintype "passive"))
      (node (ref "L3") (pin "1") (pinfunction "1_1") (pintype "passive"))
      (node (ref "R1") (pin "2") (pinfunction "2_2") (pintype "passive"))
      (node (ref "R42") (pin "2") (pinfunction "2_2") (pintype "passive"))
      (node (ref "R43") (pin "2") (pinfunction "2_2") (pintype "passive"))
      (node (ref "R48") (pin "2") (pinfunction "2_2") (pintype "passive"))
      (node (ref "R49") (pin "2") (pinfunction "2_2") (pintype "passive"))
      (node (ref "R54") (pin "1") (pinfunction "1_1") (pintype "passive"))
      (node (ref "R55") (pin "1") (pinfunction "1_1") (pintype "passive"))
      (node (ref "R58") (pin "2") (pinfunction "2_2") (pintype "passive"))
      (node (ref "U$1") (pin "P1") (pinfunction "VDD_P1") (pintype "bidirectional"))
      (node (ref "U1") (pin "105") (pinfunction "VDDIO3_105") (pintype "power_in"))
      (node (ref "U1") (pin "11") (pinfunction "VDDIO1_11") (pintype "power_in"))
      (node (ref "U1") (pin "125") (pinfunction "VDDIO4_125") (pintype "power_in"))
      (node (ref "U1") (pin "52") (pinfunction "VDDBU_52") (pintype "power_in"))
      (node (ref "U1") (pin "57") (pinfunction "VDDIN_57") (pintype "power_in"))
      (node (ref "U1") (pin "62") (pinfunction "VDDIO2_62") (pintype "power_in"))
      (node (ref "U2") (pin "2") (pinfunction "OUT_2") (pintype "passive"))
      (node (ref "U3") (pin "1") (pinfunction "VDD1_1") (pintype "power_in"))
      (node (ref "U4") (pin "1") (pinfunction "VDD1_1") (pintype "power_in"))
      (node (ref "U5") (pin "1") (pinfunction "VDD1_1") (pintype "power_in"))
      (node (ref "U6") (pin "1") (pinfunction "VDD1_1") (pintype "power_in"))
      (node (ref "U7") (pin "PIN8") (pinfunction "VCC_PIN8") (pintype "bidirectional"))
      (node (ref "U8") (pin "+VOUT") (pinfunction "+VOUT_+VOUT") (pintype "bidirectional"))
      (node (ref "WIFI") (pin "A") (pinfunction "A_A") (pintype "passive"))
    )
    (net (code "2") (name "+5V") (class "Default")
      (node (ref "AMPSEAL1") (pin "24") (pinfunction "24_24") (pintype "passive"))
      (node (ref "AMPSEAL1") (pin "25") (pinfunction "25_25") (pintype "passive"))
      (node (ref "AMPSEAL1") (pin "26") (pinfunction "26_26") (pintype "passive"))
      (node (ref "AMPSEAL1") (pin "27") (pinfunction "27_27") (pintype "passive"))
      (node (ref "AMPSEAL1") (pin "28") (pinfunction "28_28") (pintype "passive"))
      (node (ref "C48") (pin "1") (pinfunction "1_1") (pintype "passive"))
      (node (ref "C50") (pin "1") (pinfunction "1_1") (pintype "passive"))
      (node (ref "C59") (pin "1") (pinfunction "1_1") (pintype "passive"))
      (node (ref "C64") (pin "1") (pinfunction "1_1") (pintype "passive"))
      (node (ref "C68") (pin "1") (pinfunction "1_1") (pintype "passive"))
      (node (ref "C71") (pin "1") (pinfunction "1_1") (pintype "passive"))
      (node (ref "IC10") (pin "9") (pinfunction "VCC2_9") (pintype "input"))
      (node (ref "IC3") (pin "1") (pinfunction "VDD1_1") (pintype "bidirectional"))
      (node (ref "IC4") (pin "1") (pinfunction "VDD1_1") (pintype "bidirectional"))
      (node (ref "IC7") (pin "1") (pinfunction "VDD1_1") (pintype "bidirectional"))
      (node (ref "IC8") (pin "1") (pinfunction "VDD1_1") (pintype "bidirectional"))
      (node (ref "IC9") (pin "9") (pinfunction "VCC2_9") (pintype "input"))
      (node (ref "R57") (pin "2") (pinfunction "2_2") (pintype "passive"))
      (node (ref "U9") (pin "P$3") (pinfunction "VO_P$3") (pintype "bidirectional"))
    )
    (net (code "3") (name "+12V") (class "Default")
      (node (ref "AMPSEAL1") (pin "2") (pinfunction "2_2") (pintype "passive"))
      (node (ref "C32") (pin "1") (pinfunction "1_1") (pintype "passive"))
      (node (ref "C33") (pin "1") (pinfunction "1_1") (pintype "passive"))
      (node (ref "C35") (pin "1") (pinfunction "1_1") (pintype "passive"))
      (node (ref "C36") (pin "1") (pinfunction "1_1") (pintype "passive"))
      (node (ref "C38") (pin "1") (pinfunction "1_1") (pintype "passive"))
      (node (ref "C39") (pin "1") (pinfunction "1_1") (pintype "passive"))
      (node (ref "C41") (pin "1") (pinfunction "1_1") (pintype "passive"))
      (node (ref "C42") (pin "1") (pinfunction "1_1") (pintype "passive"))
      (node (ref "C74") (pin "+") (pinfunction "+_+") (pintype "passive"))
      (node (ref "C75") (pin "1") (pinfunction "1_1") (pintype "passive"))
      (node (ref "C76") (pin "1") (pinfunction "1_1") (pintype "passive"))
      (node (ref "PTC") (pin "P$1") (pinfunction "1_P$1") (pintype "passive"))
      (node (ref "R56") (pin "2") (pinfunction "2_2") (pintype "passive"))
      (node (ref "U3") (pin "8") (pinfunction "VDD2_8") (pintype "power_in"))
      (node (ref "U4") (pin "8") (pinfunction "VDD2_8") (pintype "power_in"))
      (node (ref "U5") (pin "8") (pinfunction "VDD2_8") (pintype "power_in"))
      (node (ref "U6") (pin "8") (pinfunction "VDD2_8") (pintype "power_in"))
      (node (ref "U8") (pin "+VIN1") (pinfunction "+VIN1_+VIN1") (pintype "bidirectional"))
      (node (ref "U8") (pin "+VIN2") (pinfunction "+VIN2_+VIN2") (pintype "bidirectional"))
      (node (ref "U9") (pin "P$1") (pinfunction "VI_P$1") (pintype "bidirectional"))
    )
    (net (code "4") (name "/A0") (class "Default")
      (node (ref "C55") (pin "1") (pinfunction "1_1") (pintype "passive"))
      (node (ref "IC5") (pin "6") (pinfunction "OUT_6") (pintype "output"))
      (node (ref "R26") (pin "2") (pinfunction "2_2") (pintype "passive"))
      (node (ref "U1") (pin "78") (pinfunction "PA16_78") (pintype "bidirectional"))
    )
    (net (code "5") (name "/A1") (class "Default")
      (node (ref "C44") (pin "1") (pinfunction "1_1") (pintype "passive"))
      (node (ref "IC2") (pin "6") (pinfunction "OUT_6") (pintype "output"))
      (node (ref "R15") (pin "2") (pinfunction "2_2") (pintype "passive"))
      (node (ref "U1") (pin "79") (pinfunction "PA24_79") (pintype "bidirectional"))
    )
    (net (code "6") (name "/A2") (class "Default")
      (node (ref "C56") (pin "1") (pinfunction "1_1") (pintype "passive"))
      (node (ref "IC6") (pin "6") (pinfunction "OUT_6") (pintype "output"))
      (node (ref "R27") (pin "2") (pinfunction "2_2") (pintype "passive"))
      (node (ref "U1") (pin "80") (pinfunction "PA23_80") (pintype "bidirectional"))
    )
    (net (code "7") (name "/A3") (class "Default")
      (node (ref "C43") (pin "1") (pinfunction "1_1") (pintype "passive"))
      (node (ref "IC1") (pin "6") (pinfunction "OUT_6") (pintype "output"))
      (node (ref "R14") (pin "2") (pinfunction "2_2") (pintype "passive"))
      (node (ref "U1") (pin "81") (pinfunction "PA22_81") (pintype "bidirectional"))
    )
    (net (code "8") (name "/AIN0") (class "Default")
      (node (ref "AMPSEAL1") (pin "20") (pinfunction "20_20") (pintype "passive"))
      (node (ref "R16") (pin "2") (pinfunction "2_2") (pintype "passive"))
    )
    (net (code "9") (name "/AIN1") (class "Default")
      (node (ref "AMPSEAL1") (pin "21") (pinfunction "21_21") (pintype "passive"))
      (node (ref "R30") (pin "2") (pinfunction "2_2") (pintype "passive"))
    )
    (net (code "10") (name "/AIN2") (class "Default")
      (node (ref "AMPSEAL1") (pin "22") (pinfunction "22_22") (pintype "passive"))
      (node (ref "R18") (pin "2") (pinfunction "2_2") (pintype "passive"))
    )
    (net (code "11") (name "/AIN3") (class "Default")
      (node (ref "AMPSEAL1") (pin "23") (pinfunction "23_23") (pintype "passive"))
      (node (ref "R28") (pin "2") (pinfunction "2_2") (pintype "passive"))
    )
    (net (code "12") (name "/AVREF") (class "Default")
      (node (ref "C20") (pin "1") (pinfunction "1_1") (pintype "passive"))
      (node (ref "L3") (pin "2") (pinfunction "2_2") (pintype "passive"))
      (node (ref "U1") (pin "75") (pinfunction "ADVREF_75") (pintype "power_in"))
    )
    (net (code "13") (name "/CANH0") (class "Default")
      (node (ref "AMPSEAL1") (pin "9") (pinfunction "9_9") (pintype "passive"))
      (node (ref "IC9") (pin "12") (pinfunction "CANH_12") (pintype "input"))
      (node (ref "SJ1") (pin "1") (pinfunction "1_1") (pintype "passive"))
    )
    (net (code "14") (name "/CANH1") (class "Default")
      (node (ref "AMPSEAL1") (pin "11") (pinfunction "11_11") (pintype "passive"))
      (node (ref "IC10") (pin "12") (pinfunction "CANH_12") (pintype "input"))
      (node (ref "SJ3") (pin "1") (pinfunction "1_1") (pintype "passive"))
    )
    (net (code "15") (name "/CANL0") (class "Default")
      (node (ref "AMPSEAL1") (pin "10") (pinfunction "10_10") (pintype "passive"))
      (node (ref "IC9") (pin "13") (pinfunction "CANL_13") (pintype "input"))
      (node (ref "SJ2") (pin "1") (pinfunction "1_1") (pintype "passive"))
    )
    (net (code "16") (name "/CANL1") (class "Default")
      (node (ref "AMPSEAL1") (pin "12") (pinfunction "12_12") (pintype "passive"))
      (node (ref "IC10") (pin "13") (pinfunction "CANL_13") (pintype "input"))
      (node (ref "SJ4") (pin "1") (pinfunction "1_1") (pintype "passive"))
    )
    (net (code "17") (name "/CANRX0") (class "Default")
      (node (ref "IC9") (pin "3") (pinfunction "RXD_3") (pintype "input"))
      (node (ref "U1") (pin "24") (pinfunction "PA1_24") (pintype "bidirectional"))
    )
    (net (code "18") (name "/CANRX1") (class "Default")
      (node (ref "IC10") (pin "3") (pinfunction "RXD_3") (pintype "input"))
      (node (ref "U1") (pin "76") (pinfunction "PB15_76") (pintype "bidirectional"))
    )
    (net (code "19") (name "/CANTX0") (class "Default")
      (node (ref "IC9") (pin "6") (pinfunction "TXD_6") (pintype "input"))
      (node (ref "U1") (pin "23") (pinfunction "PA0_23") (pintype "bidirectional"))
    )
    (net (code "20") (name "/CANTX1") (class "Default")
      (node (ref "IC10") (pin "6") (pinfunction "TXD_6") (pintype "input"))
      (node (ref "U1") (pin "140") (pinfunction "PB14_140") (pintype "bidirectional"))
    )
    (net (code "21") (name "/D+") (class "Default")
      (node (ref "R3") (pin "1") (pinfunction "1_1") (pintype "passive"))
      (node (ref "U1") (pin "37") (pinfunction "DHSDP_37") (pintype "bidirectional"))
      (node (ref "X1") (pin "3") (pinfunction "3_3") (pintype "passive"))
      (node (ref "Z1") (pin "1") (pinfunction "1_1") (pintype "passive"))
    )
    (net (code "22") (name "/D-") (class "Default")
      (node (ref "R2") (pin "1") (pinfunction "1_1") (pintype "passive"))
      (node (ref "U1") (pin "38") (pinfunction "DHSDM_38") (pintype "bidirectional"))
      (node (ref "X1") (pin "2") (pinfunction "2_2") (pintype "passive"))
      (node (ref "Z2") (pin "1") (pinfunction "1_1") (pintype "passive"))
    )
    (net (code "23") (name "/D2") (class "Default")
      (node (ref "U1") (pin "144") (pinfunction "PB25_144") (pintype "bidirectional"))
      (node (ref "U4") (pin "3") (pinfunction "VIB_3") (pintype "input"))
    )
    (net (code "24") (name "/D3") (class "Default")
      (node (ref "U1") (pin "139") (pinfunction "PC28_139") (pintype "bidirectional"))
      (node (ref "U4") (pin "2") (pinfunction "VIA_2") (pintype "input"))
    )
    (net (code "25") (name "/D4") (class "Default")
      (node (ref "U1") (pin "137") (pinfunction "PC26_137") (pintype "bidirectional"))
      (node (ref "U6") (pin "3") (pinfunction "VIB_3") (pintype "input"))
    )
    (net (code "26") (name "/D5") (class "Default")
      (node (ref "U1") (pin "136") (pinfunction "PC25_136") (pintype "bidirectional"))
      (node (ref "U6") (pin "2") (pinfunction "VIA_2") (pintype "input"))
    )
    (net (code "27") (name "/D6") (class "Default")
      (node (ref "U1") (pin "135") (pinfunction "PC24_135") (pintype "bidirectional"))
      (node (ref "U5") (pin "3") (pinfunction "VIB_3") (pintype "input"))
    )
    (net (code "28") (name "/D7") (class "Default")
      (node (ref "U1") (pin "134") (pinfunction "PC23_134") (pintype "bidirectional"))
      (node (ref "U5") (pin "2") (pinfunction "VIA_2") (pintype "input"))
    )
    (net (code "29") (name "/D8") (class "Default")
      (node (ref "U1") (pin "133") (pinfunction "PC22_133") (pintype "bidirectional"))
      (node (ref "U3") (pin "3") (pinfunction "VIB_3") (pintype "input"))
    )
    (net (code "30") (name "/D9") (class "Default")
      (node (ref "U1") (pin "132") (pinfunction "PC21_132") (pintype "bidirectional"))
      (node (ref "U3") (pin "2") (pinfunction "VIA_2") (pintype "input"))
    )
    (net (code "31") (name "/D13") (class "Default")
      (node (ref "R5") (pin "2") (pinfunction "2_2") (pintype "passive"))
      (node (ref "U1") (pin "68") (pinfunction "PB27_68") (pintype "bidirectional"))
    )
    (net (code "32") (name "/D18") (class "Default")
      (node (ref "U$1") (pin "P9") (pinfunction "RESET_P9") (pintype "bidirectional"))
      (node (ref "U1") (pin "4") (pinfunction "PA11_4") (pintype "bidirectional"))
    )
    (net (code "33") (name "/D42") (class "Default")
      (node (ref "U$1") (pin "P8") (pinfunction "MSEL_P8") (pintype "bidirectional"))
      (node (ref "U1") (pin "71") (pinfunction "PA19_71") (pintype "bidirectional"))
    )
    (net (code "34") (name "/D48") (class "Default")
      (node (ref "R42") (pin "1") (pinfunction "1_1") (pintype "passive"))
      (node (ref "R45") (pin "2") (pinfunction "2_2") (pintype "passive"))
      (node (ref "U1") (pin "97") (pinfunction "PC15_97") (pintype "bidirectional"))
    )
    (net (code "35") (name "/D49") (class "Default")
      (node (ref "R43") (pin "1") (pinfunction "1_1") (pintype "passive"))
      (node (ref "R47") (pin "2") (pinfunction "2_2") (pintype "passive"))
      (node (ref "U1") (pin "96") (pinfunction "PC14_96") (pintype "bidirectional"))
    )
    (net (code "36") (name "/D50") (class "Default")
      (node (ref "R48") (pin "1") (pinfunction "1_1") (pintype "passive"))
      (node (ref "R51") (pin "2") (pinfunction "2_2") (pintype "passive"))
      (node (ref "U1") (pin "95") (pinfunction "PC13_95") (pintype "bidirectional"))
    )
    (net (code "37") (name "/D51") (class "Default")
      (node (ref "R49") (pin "1") (pinfunction "1_1") (pintype "passive"))
      (node (ref "R53") (pin "2") (pinfunction "2_2") (pintype "passive"))
      (node (ref "U1") (pin "94") (pinfunction "PC12_94") (pintype "bidirectional"))
    )
    (net (code "38") (name "/DIN0") (class "Default")
      (node (ref "AMPSEAL1") (pin "32") (pinfunction "32_32") (pintype "passive"))
      (node (ref "R44") (pin "1") (pinfunction "1_1") (pintype "passive"))
    )
    (net (code "39") (name "/DIN1") (class "Default")
      (node (ref "AMPSEAL1") (pin "33") (pinfunction "33_33") (pintype "passive"))
      (node (ref "R46") (pin "1") (pinfunction "1_1") (pintype "passive"))
    )
    (net (code "40") (name "/DIN2") (class "Default")
      (node (ref "AMPSEAL1") (pin "34") (pinfunction "34_34") (pintype "passive"))
      (node (ref "R50") (pin "1") (pinfunction "1_1") (pintype "passive"))
    )
    (net (code "41") (name "/DIN3") (class "Default")
      (node (ref "AMPSEAL1") (pin "35") (pinfunction "35_35") (pintype "passive"))
      (node (ref "R52") (pin "1") (pinfunction "1_1") (pintype "passive"))
    )
    (net (code "42") (name "/DOUT0") (class "Default")
      (node (ref "AMPSEAL1") (pin "3") (pinfunction "3_3") (pintype "passive"))
      (node (ref "D1") (pin "C") (pinfunction "C_C") (pintype "passive"))
      (node (ref "T1") (pin "2") (pinfunction "D_2") (pintype "passive"))
      (node (ref "T1") (pin "4") (pinfunction "D_4") (pintype "passive"))
    )
    (net (code "43") (name "/DOUT1") (class "Default")
      (node (ref "AMPSEAL1") (pin "4") (pinfunction "4_4") (pintype "passive"))
      (node (ref "D2") (pin "C") (pinfunction "C_C") (pintype "passive"))
      (node (ref "T2") (pin "2") (pinfunction "D_2") (pintype "passive"))
      (node (ref "T2") (pin "4") (pinfunction "D_4") (pintype "passive"))
    )
    (net (code "44") (name "/DOUT2") (class "Default")
      (node (ref "AMPSEAL1") (pin "5") (pinfunction "5_5") (pintype "passive"))
      (node (ref "D3") (pin "C") (pinfunction "C_C") (pintype "passive"))
      (node (ref "T3") (pin "2") (pinfunction "D_2") (pintype "passive"))
      (node (ref "T3") (pin "4") (pinfunction "D_4") (pintype "passive"))
    )
    (net (code "45") (name "/DOUT3") (class "Default")
      (node (ref "AMPSEAL1") (pin "6") (pinfunction "6_6") (pintype "passive"))
      (node (ref "D4") (pin "C") (pinfunction "C_C") (pintype "passive"))
      (node (ref "T4") (pin "2") (pinfunction "D_2") (pintype "passive"))
      (node (ref "T4") (pin "4") (pinfunction "D_4") (pintype "passive"))
    )
    (net (code "46") (name "/DOUT4") (class "Default")
      (node (ref "AMPSEAL1") (pin "15") (pinfunction "15_15") (pintype "passive"))
      (node (ref "D5") (pin "C") (pinfunction "C_C") (pintype "passive"))
      (node (ref "T5") (pin "2") (pinfunction "D_2") (pintype "passive"))
      (node (ref "T5") (pin "4") (pinfunction "D_4") (pintype "passive"))
    )
    (net (code "47") (name "/DOUT5") (class "Default")
      (node (ref "AMPSEAL1") (pin "16") (pinfunction "16_16") (pintype "passive"))
      (node (ref "D6") (pin "C") (pinfunction "C_C") (pintype "passive"))
      (node (ref "T6") (pin "2") (pinfunction "D_2") (pintype "passive"))
      (node (ref "T6") (pin "4") (pinfunction "D_4") (pintype "passive"))
    )
    (net (code "48") (name "/DOUT6") (class "Default")
      (node (ref "AMPSEAL1") (pin "17") (pinfunction "17_17") (pintype "passive"))
      (node (ref "D7") (pin "C") (pinfunction "C_C") (pintype "passive"))
      (node (ref "T7") (pin "2") (pinfunction "D_2") (pintype "passive"))
      (node (ref "T7") (pin "4") (pinfunction "D_4") (pintype "passive"))
    )
    (net (code "49") (name "/DOUT7") (class "Default")
      (node (ref "AMPSEAL1") (pin "18") (pinfunction "18_18") (pintype "passive"))
      (node (ref "D8") (pin "C") (pinfunction "C_C") (pintype "passive"))
      (node (ref "T8") (pin "2") (pinfunction "D_2") (pintype "passive"))
      (node (ref "T8") (pin "4") (pinfunction "D_4") (pintype "passive"))
    )
    (net (code "50") (name "/GPIO0") (class "Default")
      (node (ref "JP1") (pin "8") (pinfunction "8_8") (pintype "passive"))
      (node (ref "U1") (pin "93") (pinfunction "PC11_93") (pintype "bidirectional"))
    )
    (net (code "51") (name "/GPIO1") (class "Default")
      (node (ref "JP1") (pin "7") (pinfunction "7_7") (pintype "passive"))
      (node (ref "U1") (pin "92") (pinfunction "PB21_92") (pintype "bidirectional"))
    )
    (net (code "52") (name "/GPIO2") (class "Default")
      (node (ref "JP1") (pin "5") (pinfunction "5_5") (pintype "passive"))
      (node (ref "U1") (pin "91") (pinfunction "PB20_91") (pintype "bidirectional"))
    )
    (net (code "53") (name "/GPIO3") (class "Default")
      (node (ref "JP1") (pin "3") (pinfunction "3_3") (pintype "passive"))
      (node (ref "U1") (pin "90") (pinfunction "PB19_90") (pintype "bidirectional"))
    )
    (net (code "54") (name "/GPIO4") (class "Default")
      (node (ref "JP1") (pin "1") (pinfunction "1_1") (pintype "passive"))
      (node (ref "U1") (pin "88") (pinfunction "PB17_88") (pintype "bidirectional"))
    )
    (net (code "55") (name "/MASTER-RESET") (class "Default")
      (node (ref "C28") (pin "2") (pinfunction "2_2") (pintype "passive"))
      (node (ref "RESET") (pin "P$2") (pinfunction "P$5_P$2") (pintype "bidirectional"))
      (node (ref "U1") (pin "47") (pinfunction "NRSTB_47") (pintype "input"))
    )
    (net (code "56") (name "/MDRIVE0") (class "Default")
      (node (ref "R12") (pin "1") (pinfunction "1_1") (pintype "passive"))
      (node (ref "T1") (pin "1") (pinfunction "G_1") (pintype "passive"))
      (node (ref "U6") (pin "6") (pinfunction "VOB_6") (pintype "output"))
    )
    (net (code "57") (name "/MDRIVE1") (class "Default")
      (node (ref "R13") (pin "1") (pinfunction "1_1") (pintype "passive"))
      (node (ref "T2") (pin "1") (pinfunction "G_1") (pintype "passive"))
      (node (ref "U6") (pin "7") (pinfunction "VOA_7") (pintype "output"))
    )
    (net (code "58") (name "/MDRIVE2") (class "Default")
      (node (ref "R10") (pin "1") (pinfunction "1_1") (pintype "passive"))
      (node (ref "T3") (pin "1") (pinfunction "G_1") (pintype "passive"))
      (node (ref "U5") (pin "6") (pinfunction "VOB_6") (pintype "output"))
    )
    (net (code "59") (name "/MDRIVE3") (class "Default")
      (node (ref "R11") (pin "1") (pinfunction "1_1") (pintype "passive"))
      (node (ref "T4") (pin "1") (pinfunction "G_1") (pintype "passive"))
      (node (ref "U5") (pin "7") (pinfunction "VOA_7") (pintype "output"))
    )
    (net (code "60") (name "/MDRIVE4") (class "Default")
      (node (ref "R8") (pin "1") (pinfunction "1_1") (pintype "passive"))
      (node (ref "T5") (pin "1") (pinfunction "G_1") (pintype "passive"))
      (node (ref "U4") (pin "6") (pinfunction "VOB_6") (pintype "output"))
    )
    (net (code "61") (name "/MDRIVE5") (class "Default")
      (node (ref "R9") (pin "1") (pinfunction "1_1") (pintype "passive"))
      (node (ref "T6") (pin "1") (pinfunction "G_1") (pintype "passive"))
      (node (ref "U4") (pin "7") (pinfunction "VOA_7") (pintype "output"))
    )
    (net (code "62") (name "/MDRIVE6") (class "Default")
      (node (ref "R6") (pin "1") (pinfunction "1_1") (pintype "passive"))
      (node (ref "T7") (pin "1") (pinfunction "G_1") (pintype "passive"))
      (node (ref "U3") (pin "6") (pinfunction "VOB_6") (pintype "output"))
    )
    (net (code "63") (name "/MDRIVE7") (class "Default")
      (node (ref "R7") (pin "1") (pinfunction "1_1") (pintype "passive"))
      (node (ref "T8") (pin "1") (pinfunction "G_1") (pintype "passive"))
      (node (ref "U3") (pin "7") (pinfunction "VOA_7") (pintype "output"))
    )
    (net (code "64") (name "/RX2") (class "Default")
      (node (ref "U$1") (pin "P4") (pinfunction "TXD0_P4") (pintype "bidirectional"))
      (node (ref "U1") (pin "5") (pinfunction "PA12_5") (pintype "bidirectional"))
    )
    (net (code "65") (name "/SCL") (class "Default")
      (node (ref "R54") (pin "2") (pinfunction "2_2") (pintype "passive"))
      (node (ref "U1") (pin "87") (pinfunction "PB13_87") (pintype "bidirectional"))
      (node (ref "U7") (pin "PIN6") (pinfunction "SCL_PIN6") (pintype "bidirectional"))
    )
    (net (code "66") (name "/SDA") (class "Default")
      (node (ref "R55") (pin "2") (pinfunction "2_2") (pintype "passive"))
      (node (ref "U1") (pin "86") (pinfunction "PB12_86") (pintype "bidirectional"))
      (node (ref "U7") (pin "PIN5") (pinfunction "SDA_PIN5") (pintype "bidirectional"))
    )
    (net (code "67") (name "/TX2") (class "Default")
      (node (ref "U$1") (pin "P3") (pinfunction "RXD0_P3") (pintype "bidirectional"))
      (node (ref "U1") (pin "6") (pinfunction "PA13_6") (pintype "bidirectional"))
    )
    (net (code "68") (name "/VBG") (class "Default")
      (node (ref "C27") (pin "1") (pinfunction "1_1") (pintype "passive"))
      (node (ref "R4") (pin "2") (pinfunction "2_2") (pintype "passive"))
      (node (ref "U1") (pin "40") (pinfunction "VBG_40") (pintype "passive"))
    )
    (net (code "69") (name "/VBUS") (class "Default")
      (node (ref "C29") (pin "1") (pinfunction "1_1") (pintype "passive"))
      (node (ref "U1") (pin "39") (pinfunction "VBUS_39") (pintype "power_in"))
      (node (ref "U2") (pin "3") (pinfunction "IN_3") (pintype "input"))
      (node (ref "X1") (pin "1") (pinfunction "1_1") (pintype "passive"))
    )
    (net (code "70") (name "/VDDANA") (class "Default")
      (node (ref "C10") (pin "1") (pinfunction "1_1") (pintype "passive"))
      (node (ref "C11") (pin "1") (pinfunction "1_1") (pintype "passive"))
      (node (ref "L1") (pin "2") (pinfunction "2_2") (pintype "passive"))
      (node (ref "U1") (pin "73") (pinfunction "VDDANA_73") (pintype "power_in"))
    )
    (net (code "71") (name "/VDDOUT") (class "Default")
      (node (ref "C12") (pin "1") (pinfunction "1_1") (pintype "passive"))
      (node (ref "C13") (pin "1") (pinfunction "1_1") (pintype "passive"))
      (node (ref "C14") (pin "1") (pinfunction "1_1") (pintype "passive"))
      (node (ref "C15") (pin "1") (pinfunction "1_1") (pintype "passive"))
      (node (ref "C16") (pin "1") (pinfunction "1_1") (pintype "passive"))
      (node (ref "C17") (pin "1") (pinfunction "1_1") (pintype "passive"))
      (node (ref "C18") (pin "1") (pinfunction "1_1") (pintype "passive"))
      (node (ref "L4") (pin "1") (pinfunction "1_1") (pintype "passive"))
      (node (ref "U1") (pin "10") (pinfunction "VDDCORE1_10") (pintype "input"))
      (node (ref "U1") (pin "104") (pinfunction "VDDCORE4_104") (pintype "input"))
      (node (ref "U1") (pin "124") (pinfunction "VDDCORE5_124") (pintype "input"))
      (node (ref "U1") (pin "45") (pinfunction "VDDCORE2_45") (pintype "input"))
      (node (ref "U1") (pin "56") (pinfunction "VDDOUT_56") (pintype "output"))
      (node (ref "U1") (pin "61") (pinfunction "VDDCORE3_61") (pintype "input"))
    )
    (net (code "72") (name "/VDDOUTMI") (class "Default")
      (node (ref "C8") (pin "1") (pinfunction "1_1") (pintype "passive"))
      (node (ref "C9") (pin "1") (pinfunction "1_1") (pintype "passive"))
      (node (ref "L2") (pin "2") (pinfunction "2_2") (pintype "passive"))
      (node (ref "U1") (pin "41") (pinfunction "VDDUTMI_41") (pintype "input"))
    )
    (net (code "73") (name "/VDDPLL") (class "Default")
      (node (ref "C21") (pin "1") (pinfunction "1_1") (pintype "passive"))
      (node (ref "C22") (pin "1") (pinfunction "1_1") (pintype "passive"))
      (node (ref "L4") (pin "2") (pinfunction "2_2") (pintype "passive"))
      (node (ref "U1") (pin "34") (pinfunction "VDDPLL_34") (pintype "input"))
    )
    (net (code "74") (name "/VIN(+12V)") (class "Default")
      (node (ref "AMPSEAL1") (pin "1") (pinfunction "1_1") (pintype "passive"))
      (node (ref "D9") (pin "A") (pinfunction "A_A") (pintype "passive"))
    )
    (net (code "75") (name "/XIN") (class "Default")
      (node (ref "C24") (pin "1") (pinfunction "1_1") (pintype "passive"))
      (node (ref "U1") (pin "36") (pinfunction "XIN_36") (pintype "input"))
      (node (ref "Y1") (pin "1") (pinfunction "C1_1") (pintype "passive"))
    )
    (net (code "76") (name "/XIN32") (class "Default")
      (node (ref "C26") (pin "1") (pinfunction "1_1") (pintype "passive"))
      (node (ref "U1") (pin "48") (pinfunction "XIN32_48") (pintype "output"))
      (node (ref "Y2") (pin "P$2") (pinfunction "2_P$2") (pintype "bidirectional"))
    )
    (net (code "77") (name "/XOUT") (class "Default")
      (node (ref "C23") (pin "1") (pinfunction "1_1") (pintype "passive"))
      (node (ref "U1") (pin "35") (pinfunction "XOUT_35") (pintype "output"))
      (node (ref "Y1") (pin "3") (pinfunction "C2_3") (pintype "passive"))
    )
    (net (code "78") (name "/XOUT32") (class "Default")
      (node (ref "C25") (pin "1") (pinfunction "1_1") (pintype "passive"))
      (node (ref "U1") (pin "49") (pinfunction "XOUT32_49") (pintype "output"))
      (node (ref "Y2") (pin "P$1") (pinfunction "1_P$1") (pintype "bidirectional"))
    )
    (net (code "79") (name "GND") (class "Default")
      (node (ref "+12V") (pin "C") (pinfunction "C_C") (pintype "passive"))
      (node (ref "+5V") (pin "C") (pinfunction "C_C") (pintype "passive"))
      (node (ref "AMPSEAL1") (pin "13") (pinfunction "13_13") (pintype "passive"))
      (node (ref "AMPSEAL1") (pin "14") (pinfunction "14_14") (pintype "passive"))
      (node (ref "AMPSEAL1") (pin "19") (pinfunction "19_19") (pintype "passive"))
      (node (ref "AMPSEAL1") (pin "29") (pinfunction "29_29") (pintype "passive"))
      (node (ref "AMPSEAL1") (pin "30") (pinfunction "30_30") (pintype "passive"))
      (node (ref "AMPSEAL1") (pin "31") (pinfunction "31_31") (pintype "passive"))
      (node (ref "AMPSEAL1") (pin "7") (pinfunction "7_7") (pintype "passive"))
      (node (ref "AMPSEAL1") (pin "8") (pinfunction "8_8") (pintype "passive"))
      (node (ref "C32") (pin "2") (pinfunction "2_2") (pintype "passive"))
      (node (ref "C33") (pin "2") (pinfunction "2_2") (pintype "passive"))
      (node (ref "C35") (pin "2") (pinfunction "2_2") (pintype "passive"))
      (node (ref "C36") (pin "2") (pinfunction "2_2") (pintype "passive"))
      (node (ref "C38") (pin "2") (pinfunction "2_2") (pintype "passive"))
      (node (ref "C39") (pin "2") (pinfunction "2_2") (pintype "passive"))
      (node (ref "C41") (pin "2") (pinfunction "2_2") (pintype "passive"))
      (node (ref "C42") (pin "2") (pinfunction "2_2") (pintype "passive"))
      (node (ref "C47") (pin "2") (pinfunction "2_2") (pintype "passive"))
      (node (ref "C48") (pin "2") (pinfunction "2_2") (pintype "passive"))
      (node (ref "C49") (pin "2") (pinfunction "2_2") (pintype "passive"))
      (node (ref "C50") (pin "2") (pinfunction "2_2") (pintype "passive"))
      (node (ref "C58") (pin "2") (pinfunction "2_2") (pintype "passive"))
      (node (ref "C59") (pin "2") (pinfunction "2_2") (pintype "passive"))
      (node (ref "C63") (pin "2") (pinfunction "2_2") (pintype "passive"))
      (node (ref "C64") (pin "2") (pinfunction "2_2") (pintype "passive"))
      (node (ref "C68") (pin "2") (pinfunction "2_2") (pintype "passive"))
      (node (ref "C69") (pin "2") (pinfunction "2_2") (pintype "passive"))
      (node (ref "C71") (pin "2") (pinfunction "2_2") (pintype "passive"))
      (node (ref "C72") (pin "2") (pinfunction "2_2") (pintype "passive"))
      (node (ref "C74") (pin "-") (pinfunction "-_-") (pintype "passive"))
      (node (ref "C75") (pin "2") (pinfunction "2_2") (pintype "passive"))
      (node (ref "C76") (pin "2") (pinfunction "2_2") (pintype "passive"))
      (node (ref "C78") (pin "1") (pinfunction "1_1") (pintype "passive"))
      (node (ref "D1") (pin "A") (pinfunction "A_A") (pintype "passive"))
      (node (ref "D2") (pin "A") (pinfunction "A_A") (pintype "passive"))
      (node (ref "D3") (pin "A") (pinfunction "A_A") (pintype "passive"))
      (node (ref "D4") (pin "A") (pinfunction "A_A") (pintype "passive"))
      (node (ref "D5") (pin "A") (pinfunction "A_A") (pintype "passive"))
      (node (ref "D6") (pin "A") (pinfunction "A_A") (pintype "passive"))
      (node (ref "D7") (pin "A") (pinfunction "A_A") (pintype "passive"))
      (node (ref "D8") (pin "A") (pinfunction "A_A") (pintype "passive"))
      (node (ref "IC10") (pin "10") (pinfunction "GND2_10") (pintype "input"))
      (node (ref "IC10") (pin "15") (pinfunction "GND2_15") (pintype "input"))
      (node (ref "IC10") (pin "16") (pinfunction "GND2_16") (pintype "input"))
      (node (ref "IC3") (pin "3") (pinfunction "SHDN_3") (pintype "bidirectional"))
      (node (ref "IC3") (pin "4") (pinfunction "GND1_4") (pintype "bidirectional"))
      (node (ref "IC4") (pin "3") (pinfunction "SHDN_3") (pintype "bidirectional"))
      (node (ref "IC4") (pin "4") (pinfunction "GND1_4") (pintype "bidirectional"))
      (node (ref "IC7") (pin "3") (pinfunction "SHDN_3") (pintype "bidirectional"))
      (node (ref "IC7") (pin "4") (pinfunction "GND1_4") (pintype "bidirectional"))
      (node (ref "IC8") (pin "3") (pinfunction "SHDN_3") (pintype "bidirectional"))
      (node (ref "IC8") (pin "4") (pinfunction "GND1_4") (pintype "bidirectional"))
      (node (ref "IC9") (pin "10") (pinfunction "GND2_10") (pintype "input"))
      (node (ref "IC9") (pin "15") (pinfunction "GND2_15") (pintype "input"))
      (node (ref "IC9") (pin "16") (pinfunction "GND2_16") (pintype "input"))
      (node (ref "OK1") (pin "2") (pinfunction "C_2") (pintype "passive"))
      (node (ref "OK1") (pin "4") (pinfunction "C_4") (pintype "passive"))
      (node (ref "OK2") (pin "2") (pinfunction "C_2") (pintype "passive"))
      (node (ref "OK2") (pin "4") (pinfunction "C_4") (pintype "passive"))
      (node (ref "R10") (pin "2") (pinfunction "2_2") (pintype "passive"))
      (node (ref "R11") (pin "2") (pinfunction "2_2") (pintype "passive"))
      (node (ref "R12") (pin "2") (pinfunction "2_2") (pintype "passive"))
      (node (ref "R13") (pin "2") (pinfunction "2_2") (pintype "passive"))
      (node (ref "R20") (pin "1") (pinfunction "1_1") (pintype "passive"))
      (node (ref "R22") (pin "1") (pinfunction "1_1") (pintype "passive"))
      (node (ref "R32") (pin "1") (pinfunction "1_1") (pintype "passive"))
      (node (ref "R34") (pin "1") (pinfunction "1_1") (pintype "passive"))
      (node (ref "R6") (pin "2") (pinfunction "2_2") (pintype "passive"))
      (node (ref "R7") (pin "2") (pinfunction "2_2") (pintype "passive"))
      (node (ref "R8") (pin "2") (pinfunction "2_2") (pintype "passive"))
      (node (ref "R9") (pin "2") (pinfunction "2_2") (pintype "passive"))
      (node (ref "T1") (pin "3") (pinfunction "S_3") (pintype "passive"))
      (node (ref "T2") (pin "3") (pinfunction "S_3") (pintype "passive"))
      (node (ref "T3") (pin "3") (pinfunction "S_3") (pintype "passive"))
      (node (ref "T4") (pin "3") (pinfunction "S_3") (pintype "passive"))
      (node (ref "T5") (pin "3") (pinfunction "S_3") (pintype "passive"))
      (node (ref "T6") (pin "3") (pinfunction "S_3") (pintype "passive"))
      (node (ref "T7") (pin "3") (pinfunction "S_3") (pintype "passive"))
      (node (ref "T8") (pin "3") (pinfunction "S_3") (pintype "passive"))
      (node (ref "TVS") (pin "A") (pinfunction "A_A") (pintype "passive"))
      (node (ref "U3") (pin "5") (pinfunction "GND2_5") (pintype "passive"))
      (node (ref "U4") (pin "5") (pinfunction "GND2_5") (pintype "passive"))
      (node (ref "U5") (pin "5") (pinfunction "GND2_5") (pintype "passive"))
      (node (ref "U6") (pin "5") (pinfunction "GND2_5") (pintype "passive"))
      (node (ref "U8") (pin "-VIN1") (pinfunction "-VIN1_-VIN1") (pintype "bidirectional"))
      (node (ref "U8") (pin "-VIN2") (pinfunction "-VIN2_-VIN2") (pintype "bidirectional"))
      (node (ref "U9") (pin "P$2") (pinfunction "GND_P$2") (pintype "bidirectional"))
      (node (ref "ZEN") (pin "A") (pinfunction "A_A") (pintype "passive"))
    )
    (net (code "80") (name "IGND") (class "Default")
      (node (ref "+3.3V") (pin "C") (pinfunction "C_C") (pintype "passive"))
      (node (ref "C1") (pin "2") (pinfunction "2_2") (pintype "passive"))
      (node (ref "C10") (pin "2") (pinfunction "2_2") (pintype "passive"))
      (node (ref "C11") (pin "2") (pinfunction "2_2") (pintype "passive"))
      (node (ref "C12") (pin "2") (pinfunction "2_2") (pintype "passive"))
      (node (ref "C13") (pin "2") (pinfunction "2_2") (pintype "passive"))
      (node (ref "C14") (pin "2") (pinfunction "2_2") (pintype "passive"))
      (node (ref "C15") (pin "2") (pinfunction "2_2") (pintype "passive"))
      (node (ref "C16") (pin "2") (pinfunction "2_2") (pintype "passive"))
      (node (ref "C17") (pin "2") (pinfunction "2_2") (pintype "passive"))
      (node (ref "C18") (pin "2") (pinfunction "2_2") (pintype "passive"))
      (node (ref "C19") (pin "2") (pinfunction "2_2") (pintype "passive"))
      (node (ref "C2") (pin "2") (pinfunction "2_2") (pintype "passive"))
      (node (ref "C20") (pin "2") (pinfunction "2_2") (pintype "passive"))
      (node (ref "C21") (pin "2") (pinfunction "2_2") (pintype "passive"))
      (node (ref "C22") (pin "2") (pinfunction "2_2") (pintype "passive"))
      (node (ref "C23") (pin "2") (pinfunction "2_2") (pintype "passive"))
      (node (ref "C24") (pin "2") (pinfunction "2_2") (pintype "passive"))
      (node (ref "C25") (pin "2") (pinfunction "2_2") (pintype "passive"))
      (node (ref "C26") (pin "2") (pinfunction "2_2") (pintype "passive"))
      (node (ref "C27") (pin "2") (pinfunction "2_2") (pintype "passive"))
      (node (ref "C29") (pin "2") (pinfunction "2_2") (pintype "passive"))
      (node (ref "C3") (pin "2") (pinfunction "2_2") (pintype "passive"))
      (node (ref "C30") (pin "2") (pinfunction "2_2") (pintype "passive"))
      (node (ref "C31") (pin "2") (pinfunction "2_2") (pintype "passive"))
      (node (ref "C34") (pin "2") (pinfunction "2_2") (pintype "passive"))
      (node (ref "C37") (pin "2") (pinfunction "2_2") (pintype "passive"))
      (node (ref "C4") (pin "2") (pinfunction "2_2") (pintype "passive"))
      (node (ref "C40") (pin "2") (pinfunction "2_2") (pintype "passive"))
      (node (ref "C45") (pin "2") (pinfunction "2_2") (pintype "passive"))
      (node (ref "C46") (pin "2") (pinfunction "2_2") (pintype "passive"))
      (node (ref "C5") (pin "2") (pinfunction "2_2") (pintype "passive"))
      (node (ref "C51") (pin "2") (pinfunction "2_2") (pintype "passive"))
      (node (ref "C52") (pin "2") (pinfunction "2_2") (pintype "passive"))
      (node (ref "C53") (pin "2") (pinfunction "2_2") (pintype "passive"))
      (node (ref "C54") (pin "2") (pinfunction "2_2") (pintype "passive"))
      (node (ref "C57") (pin "2") (pinfunction "2_2") (pintype "passive"))
      (node (ref "C6") (pin "2") (pinfunction "2_2") (pintype "passive"))
      (node (ref "C60") (pin "2") (pinfunction "2_2") (pintype "passive"))
      (node (ref "C61") (pin "2") (pinfunction "2_2") (pintype "passive"))
      (node (ref "C62") (pin "2") (pinfunction "2_2") (pintype "passive"))
      (node (ref "C65") (pin "2") (pinfunction "2_2") (pintype "passive"))
      (node (ref "C66") (pin "2") (pinfunction "2_2") (pintype "passive"))
      (node (ref "C67") (pin "2") (pinfunction "2_2") (pintype "passive"))
      (node (ref "C7") (pin "2") (pinfunction "2_2") (pintype "passive"))
      (node (ref "C70") (pin "2") (pinfunction "2_2") (pintype "passive"))
      (node (ref "C73") (pin "2") (pinfunction "2_2") (pintype "passive"))
      (node (ref "C77") (pin "2") (pinfunction "2_2") (pintype "passive"))
      (node (ref "C78") (pin "2") (pinfunction "2_2") (pintype "passive"))
      (node (ref "C79") (pin "2") (pinfunction "2_2") (pintype "passive"))
      (node (ref "C8") (pin "2") (pinfunction "2_2") (pintype "passive"))
      (node (ref "C9") (pin "2") (pinfunction "2_2") (pintype "passive"))
      (node (ref "IC1") (pin "4") (pinfunction "V-_4") (pintype "power_in"))
      (node (ref "IC10") (pin "2") (pinfunction "GND1_2") (pintype "input"))
      (node (ref "IC10") (pin "7") (pinfunction "GND1_7") (pintype "input"))
      (node (ref "IC10") (pin "8") (pinfunction "GND1_8") (pintype "input"))
      (node (ref "IC2") (pin "4") (pinfunction "V-_4") (pintype "power_in"))
      (node (ref "IC3") (pin "5") (pinfunction "GND2_5") (pintype "bidirectional"))
      (node (ref "IC4") (pin "5") (pinfunction "GND2_5") (pintype "bidirectional"))
      (node (ref "IC5") (pin "4") (pinfunction "V-_4") (pintype "power_in"))
      (node (ref "IC6") (pin "4") (pinfunction "V-_4") (pintype "power_in"))
      (node (ref "IC7") (pin "5") (pinfunction "GND2_5") (pintype "bidirectional"))
      (node (ref "IC8") (pin "5") (pinfunction "GND2_5") (pintype "bidirectional"))
      (node (ref "IC9") (pin "2") (pinfunction "GND1_2") (pintype "input"))
      (node (ref "IC9") (pin "7") (pinfunction "GND1_7") (pintype "input"))
      (node (ref "IC9") (pin "8") (pinfunction "GND1_8") (pintype "input"))
      (node (ref "JP1") (pin "4") (pinfunction "4_4") (pintype "passive"))
      (node (ref "LED") (pin "C") (pinfunction "C_C") (pintype "passive"))
      (node (ref "OK1") (pin "5") (pinfunction "EMIT_5") (pintype "passive"))
      (node (ref "OK1") (pin "7") (pinfunction "EMIT_7") (pintype "passive"))
      (node (ref "OK2") (pin "5") (pinfunction "EMIT_5") (pintype "passive"))
      (node (ref "OK2") (pin "7") (pinfunction "EMIT_7") (pintype "passive"))
      (node (ref "R24") (pin "2") (pinfunction "2_2") (pintype "passive"))
      (node (ref "R25") (pin "2") (pinfunction "2_2") (pintype "passive"))
      (node (ref "R36") (pin "2") (pinfunction "2_2") (pintype "passive"))
      (node (ref "R37") (pin "2") (pinfunction "2_2") (pintype "passive"))
      (node (ref "R4") (pin "1") (pinfunction "1_1") (pintype "passive"))
      (node (ref "RESET") (pin "P$1") (pinfunction "P$4_P$1") (pintype "bidirectional"))
      (node (ref "U$1") (pin "P2") (pinfunction "GND_P2") (pintype "bidirectional"))
      (node (ref "U1") (pin "106") (pinfunction "GND3_106") (pintype "power_in"))
      (node (ref "U1") (pin "12") (pinfunction "GND1_12") (pintype "power_in"))
      (node (ref "U1") (pin "126") (pinfunction "GND4_126") (pintype "power_in"))
      (node (ref "U1") (pin "33") (pinfunction "GNDPLL_33") (pintype "power_in"))
      (node (ref "U1") (pin "44") (pinfunction "GNDUTMI_44") (pintype "power_in"))
      (node (ref "U1") (pin "46") (pinfunction "JTAGSEL_46") (pintype "input"))
      (node (ref "U1") (pin "54") (pinfunction "GNDBU_54") (pintype "power_in"))
      (node (ref "U1") (pin "58") (pinfunction "GND2_58") (pintype "power_in"))
      (node (ref "U1") (pin "74") (pinfunction "GNDANA_74") (pintype "power_in"))
      (node (ref "U2") (pin "1") (pinfunction "ADJ_1") (pintype "input"))
      (node (ref "U3") (pin "4") (pinfunction "GND1_4") (pintype "passive"))
      (node (ref "U4") (pin "4") (pinfunction "GND1_4") (pintype "passive"))
      (node (ref "U5") (pin "4") (pinfunction "GND1_4") (pintype "passive"))
      (node (ref "U6") (pin "4") (pinfunction "GND1_4") (pintype "passive"))
      (node (ref "U7") (pin "PIN1") (pinfunction "NA1_PIN1") (pintype "bidirectional"))
      (node (ref "U7") (pin "PIN2") (pinfunction "NA2_PIN2") (pintype "bidirectional"))
      (node (ref "U7") (pin "PIN3") (pinfunction "E2_PIN3") (pintype "bidirectional"))
      (node (ref "U7") (pin "PIN4") (pinfunction "VSS_PIN4") (pintype "bidirectional"))
      (node (ref "U8") (pin "-VOUT") (pinfunction "-VOUT_-VOUT") (pintype "bidirectional"))
      (node (ref "X1") (pin "4") (pinfunction "4_4") (pintype "passive"))
      (node (ref "Y1") (pin "2") (pinfunction "GND_2") (pintype "passive"))
      (node (ref "Y1") (pin "4") (pinfunction "GND_4") (pintype "passive"))
      (node (ref "Z1") (pin "2") (pinfunction "2_2") (pintype "passive"))
      (node (ref "Z2") (pin "2") (pinfunction "2_2") (pintype "passive"))
    )
    (net (code "81") (name "Net-(+3.3V-PadA)") (class "Default")
      (node (ref "+3.3V") (pin "A") (pinfunction "A_A") (pintype "passive"))
      (node (ref "R58") (pin "1") (pinfunction "1_1") (pintype "passive"))
    )
    (net (code "82") (name "Net-(+5V-PadA)") (class "Default")
      (node (ref "+5V") (pin "A") (pinfunction "A_A") (pintype "passive"))
      (node (ref "R57") (pin "1") (pinfunction "1_1") (pintype "passive"))
    )
    (net (code "83") (name "Net-(+12V-PadA)") (class "Default")
      (node (ref "+12V") (pin "A") (pinfunction "A_A") (pintype "passive"))
      (node (ref "R56") (pin "1") (pinfunction "1_1") (pintype "passive"))
    )
    (net (code "84") (name "Net-(C69-Pad1)") (class "Default")
      (node (ref "C69") (pin "1") (pinfunction "1_1") (pintype "passive"))
      (node (ref "R38") (pin "1") (pinfunction "1_1") (pintype "passive"))
      (node (ref "R39") (pin "1") (pinfunction "1_1") (pintype "passive"))
    )
    (net (code "85") (name "Net-(C72-Pad1)") (class "Default")
      (node (ref "C72") (pin "1") (pinfunction "1_1") (pintype "passive"))
      (node (ref "R40") (pin "1") (pinfunction "1_1") (pintype "passive"))
      (node (ref "R41") (pin "1") (pinfunction "1_1") (pintype "passive"))
    )
    (net (code "86") (name "Net-(ERASE-P$4)") (class "Default")
      (node (ref "ERASE") (pin "P$1") (pinfunction "P$4_P$1") (pintype "bidirectional"))
      (node (ref "U1") (pin "130") (pinfunction "PC0_130") (pintype "bidirectional"))
    )
    (net (code "87") (name "Net-(IC1-+IN)") (class "Default")
      (node (ref "C53") (pin "1") (pinfunction "1_1") (pintype "passive"))
      (node (ref "IC1") (pin "3") (pinfunction "+IN_3") (pintype "input"))
      (node (ref "R21") (pin "2") (pinfunction "2_2") (pintype "passive"))
      (node (ref "R24") (pin "1") (pinfunction "1_1") (pintype "passive"))
    )
    (net (code "88") (name "Net-(IC1--IN)") (class "Default")
      (node (ref "C43") (pin "2") (pinfunction "2_2") (pintype "passive"))
      (node (ref "IC1") (pin "2") (pinfunction "-IN_2") (pintype "input"))
      (node (ref "R14") (pin "1") (pinfunction "1_1") (pintype "passive"))
      (node (ref "R17") (pin "2") (pinfunction "2_2") (pintype "passive"))
    )
    (net (code "89") (name "Net-(IC2-+IN)") (class "Default")
      (node (ref "C54") (pin "1") (pinfunction "1_1") (pintype "passive"))
      (node (ref "IC2") (pin "3") (pinfunction "+IN_3") (pintype "input"))
      (node (ref "R23") (pin "2") (pinfunction "2_2") (pintype "passive"))
      (node (ref "R25") (pin "1") (pinfunction "1_1") (pintype "passive"))
    )
    (net (code "90") (name "Net-(IC2--IN)") (class "Default")
      (node (ref "C44") (pin "2") (pinfunction "2_2") (pintype "passive"))
      (node (ref "IC2") (pin "2") (pinfunction "-IN_2") (pintype "input"))
      (node (ref "R15") (pin "1") (pinfunction "1_1") (pintype "passive"))
      (node (ref "R19") (pin "2") (pinfunction "2_2") (pintype "passive"))
    )
    (net (code "91") (name "Net-(IC3-VIN)") (class "Default")
      (node (ref "C47") (pin "1") (pinfunction "1_1") (pintype "passive"))
      (node (ref "IC3") (pin "2") (pinfunction "VIN_2") (pintype "bidirectional"))
      (node (ref "R16") (pin "1") (pinfunction "1_1") (pintype "passive"))
      (node (ref "R20") (pin "2") (pinfunction "2_2") (pintype "passive"))
    )
    (net (code "92") (name "Net-(IC3-VOUT+)") (class "Default")
      (node (ref "IC3") (pin "7") (pinfunction "VOUT+_7") (pintype "bidirectional"))
      (node (ref "R21") (pin "1") (pinfunction "1_1") (pintype "passive"))
    )
    (net (code "93") (name "Net-(IC3-VOUT-)") (class "Default")
      (node (ref "IC3") (pin "6") (pinfunction "VOUT-_6") (pintype "bidirectional"))
      (node (ref "R17") (pin "1") (pinfunction "1_1") (pintype "passive"))
    )
    (net (code "94") (name "Net-(IC4-VIN)") (class "Default")
      (node (ref "C49") (pin "1") (pinfunction "1_1") (pintype "passive"))
      (node (ref "IC4") (pin "2") (pinfunction "VIN_2") (pintype "bidirectional"))
      (node (ref "R18") (pin "1") (pinfunction "1_1") (pintype "passive"))
      (node (ref "R22") (pin "2") (pinfunction "2_2") (pintype "passive"))
    )
    (net (code "95") (name "Net-(IC4-VOUT+)") (class "Default")
      (node (ref "IC4") (pin "7") (pinfunction "VOUT+_7") (pintype "bidirectional"))
      (node (ref "R23") (pin "1") (pinfunction "1_1") (pintype "passive"))
    )
    (net (code "96") (name "Net-(IC4-VOUT-)") (class "Default")
      (node (ref "IC4") (pin "6") (pinfunction "VOUT-_6") (pintype "bidirectional"))
      (node (ref "R19") (pin "1") (pinfunction "1_1") (pintype "passive"))
    )
    (net (code "97") (name "Net-(IC5-+IN)") (class "Default")
      (node (ref "C62") (pin "1") (pinfunction "1_1") (pintype "passive"))
      (node (ref "IC5") (pin "3") (pinfunction "+IN_3") (pintype "input"))
      (node (ref "R33") (pin "2") (pinfunction "2_2") (pintype "passive"))
      (node (ref "R36") (pin "1") (pinfunction "1_1") (pintype "passive"))
    )
    (net (code "98") (name "Net-(IC5--IN)") (class "Default")
      (node (ref "C55") (pin "2") (pinfunction "2_2") (pintype "passive"))
      (node (ref "IC5") (pin "2") (pinfunction "-IN_2") (pintype "input"))
      (node (ref "R26") (pin "1") (pinfunction "1_1") (pintype "passive"))
      (node (ref "R29") (pin "2") (pinfunction "2_2") (pintype "passive"))
    )
    (net (code "99") (name "Net-(IC6-+IN)") (class "Default")
      (node (ref "C66") (pin "1") (pinfunction "1_1") (pintype "passive"))
      (node (ref "IC6") (pin "3") (pinfunction "+IN_3") (pintype "input"))
      (node (ref "R35") (pin "2") (pinfunction "2_2") (pintype "passive"))
      (node (ref "R37") (pin "1") (pinfunction "1_1") (pintype "passive"))
    )
    (net (code "100") (name "Net-(IC6--IN)") (class "Default")
      (node (ref "C56") (pin "2") (pinfunction "2_2") (pintype "passive"))
      (node (ref "IC6") (pin "2") (pinfunction "-IN_2") (pintype "input"))
      (node (ref "R27") (pin "1") (pinfunction "1_1") (pintype "passive"))
      (node (ref "R31") (pin "2") (pinfunction "2_2") (pintype "passive"))
    )
    (net (code "101") (name "Net-(IC7-VIN)") (class "Default")
      (node (ref "C58") (pin "1") (pinfunction "1_1") (pintype "passive"))
      (node (ref "IC7") (pin "2") (pinfunction "VIN_2") (pintype "bidirectional"))
      (node (ref "R28") (pin "1") (pinfunction "1_1") (pintype "passive"))
      (node (ref "R32") (pin "2") (pinfunction "2_2") (pintype "passive"))
    )
    (net (code "102") (name "Net-(IC7-VOUT+)") (class "Default")
      (node (ref "IC7") (pin "7") (pinfunction "VOUT+_7") (pintype "bidirectional"))
      (node (ref "R33") (pin "1") (pinfunction "1_1") (pintype "passive"))
    )
    (net (code "103") (name "Net-(IC7-VOUT-)") (class "Default")
      (node (ref "IC7") (pin "6") (pinfunction "VOUT-_6") (pintype "bidirectional"))
      (node (ref "R29") (pin "1") (pinfunction "1_1") (pintype "passive"))
    )
    (net (code "104") (name "Net-(IC8-VIN)") (class "Default")
      (node (ref "C63") (pin "1") (pinfunction "1_1") (pintype "passive"))
      (node (ref "IC8") (pin "2") (pinfunction "VIN_2") (pintype "bidirectional"))
      (node (ref "R30") (pin "1") (pinfunction "1_1") (pintype "passive"))
      (node (ref "R34") (pin "2") (pinfunction "2_2") (pintype "passive"))
    )
    (net (code "105") (name "Net-(IC8-VOUT+)") (class "Default")
      (node (ref "IC8") (pin "7") (pinfunction "VOUT+_7") (pintype "bidirectional"))
      (node (ref "R35") (pin "1") (pinfunction "1_1") (pintype "passive"))
    )
    (net (code "106") (name "Net-(IC8-VOUT-)") (class "Default")
      (node (ref "IC8") (pin "6") (pinfunction "VOUT-_6") (pintype "bidirectional"))
      (node (ref "R31") (pin "1") (pinfunction "1_1") (pintype "passive"))
    )
    (net (code "107") (name "Net-(LED-PadA)") (class "Default")
      (node (ref "LED") (pin "A") (pinfunction "A_A") (pintype "passive"))
      (node (ref "R5") (pin "1") (pinfunction "1_1") (pintype "passive"))
    )
    (net (code "108") (name "Net-(OK1A-A)") (class "Default")
      (node (ref "OK1") (pin "1") (pinfunction "A_1") (pintype "passive"))
      (node (ref "R44") (pin "2") (pinfunction "2_2") (pintype "passive"))
    )
    (net (code "109") (name "Net-(OK1A-COL)") (class "Default")
      (node (ref "OK1") (pin "8") (pinfunction "COL_8") (pintype "passive"))
      (node (ref "R45") (pin "1") (pinfunction "1_1") (pintype "passive"))
    )
    (net (code "110") (name "Net-(OK1B-A)") (class "Default")
      (node (ref "OK1") (pin "3") (pinfunction "A_3") (pintype "passive"))
      (node (ref "R46") (pin "2") (pinfunction "2_2") (pintype "passive"))
    )
    (net (code "111") (name "Net-(OK1B-COL)") (class "Default")
      (node (ref "OK1") (pin "6") (pinfunction "COL_6") (pintype "passive"))
      (node (ref "R47") (pin "1") (pinfunction "1_1") (pintype "passive"))
    )
    (net (code "112") (name "Net-(OK2A-A)") (class "Default")
      (node (ref "OK2") (pin "1") (pinfunction "A_1") (pintype "passive"))
      (node (ref "R50") (pin "2") (pinfunction "2_2") (pintype "passive"))
    )
    (net (code "113") (name "Net-(OK2A-COL)") (class "Default")
      (node (ref "OK2") (pin "8") (pinfunction "COL_8") (pintype "passive"))
      (node (ref "R51") (pin "1") (pinfunction "1_1") (pintype "passive"))
    )
    (net (code "114") (name "Net-(OK2B-A)") (class "Default")
      (node (ref "OK2") (pin "3") (pinfunction "A_3") (pintype "passive"))
      (node (ref "R52") (pin "2") (pinfunction "2_2") (pintype "passive"))
    )
    (net (code "115") (name "Net-(OK2B-COL)") (class "Default")
      (node (ref "OK2") (pin "6") (pinfunction "COL_6") (pintype "passive"))
      (node (ref "R53") (pin "1") (pinfunction "1_1") (pintype "passive"))
    )
    (net (code "116") (name "Net-(PTC-2)") (class "Default")
      (node (ref "D9") (pin "C") (pinfunction "C_C") (pintype "passive"))
      (node (ref "PTC") (pin "P$2") (pinfunction "2_P$2") (pintype "passive"))
      (node (ref "TVS") (pin "C") (pinfunction "C_C") (pintype "passive"))
      (node (ref "ZEN") (pin "C") (pinfunction "C_C") (pintype "passive"))
    )
    (net (code "117") (name "Net-(R38-Pad2)") (class "Default")
      (node (ref "R38") (pin "2") (pinfunction "2_2") (pintype "passive"))
      (node (ref "SJ1") (pin "2") (pinfunction "2_2") (pintype "passive"))
    )
    (net (code "118") (name "Net-(R39-Pad2)") (class "Default")
      (node (ref "R39") (pin "2") (pinfunction "2_2") (pintype "passive"))
      (node (ref "SJ2") (pin "2") (pinfunction "2_2") (pintype "passive"))
    )
    (net (code "119") (name "Net-(R40-Pad2)") (class "Default")
      (node (ref "R40") (pin "2") (pinfunction "2_2") (pintype "passive"))
      (node (ref "SJ3") (pin "2") (pinfunction "2_2") (pintype "passive"))
    )
    (net (code "120") (name "Net-(R41-Pad2)") (class "Default")
      (node (ref "R41") (pin "2") (pinfunction "2_2") (pintype "passive"))
      (node (ref "SJ4") (pin "2") (pinfunction "2_2") (pintype "passive"))
    )
    (net (code "121") (name "Net-(U$1-CTS0)") (class "Default")
      (node (ref "U$1") (pin "P5") (pinfunction "CTS0_P5") (pintype "bidirectional"))
      (node (ref "U$1") (pin "P6") (pinfunction "RTS0_P6") (pintype "bidirectional"))
    )
    (net (code "122") (name "Net-(U$1-RF_LED)") (class "Default")
      (node (ref "U$1") (pin "P10") (pinfunction "RF_LED_P10") (pintype "bidirectional"))
      (node (ref "WIFI") (pin "C") (pinfunction "C_C") (pintype "passive"))
    )
    (net (code "123") (name "Net-(U1-DFSDM)") (class "Default")
      (node (ref "R2") (pin "2") (pinfunction "2_2") (pintype "passive"))
      (node (ref "U1") (pin "43") (pinfunction "DFSDM_43") (pintype "input"))
    )
    (net (code "124") (name "Net-(U1-DFSDP)") (class "Default")
      (node (ref "R3") (pin "2") (pinfunction "2_2") (pintype "passive"))
      (node (ref "U1") (pin "42") (pinfunction "DFSDP_42") (pintype "input"))
    )
    (net (code "125") (name "Net-(U1-FWUP)") (class "Default")
      (node (ref "R1") (pin "1") (pinfunction "1_1") (pintype "passive"))
      (node (ref "U1") (pin "53") (pinfunction "FWUP_53") (pintype "input"))
    )
    (net (code "126") (name "unconnected-(IC1-NC-Pad8)") (class "Default")
      (node (ref "IC1") (pin "8") (pinfunction "NC_8") (pintype "no_connect"))
    )
    (net (code "127") (name "unconnected-(IC1-REF-Pad1)") (class "Default")
      (node (ref "IC1") (pin "1") (pinfunction "REF_1") (pintype "passive"))
    )
    (net (code "128") (name "unconnected-(IC1-SENSE-Pad5)") (class "Default")
      (node (ref "IC1") (pin "5") (pinfunction "SENSE_5") (pintype "passive"))
    )
    (net (code "129") (name "unconnected-(IC2-NC-Pad8)") (class "Default")
      (node (ref "IC2") (pin "8") (pinfunction "NC_8") (pintype "no_connect"))
    )
    (net (code "130") (name "unconnected-(IC2-REF-Pad1)") (class "Default")
      (node (ref "IC2") (pin "1") (pinfunction "REF_1") (pintype "passive"))
    )
    (net (code "131") (name "unconnected-(IC2-SENSE-Pad5)") (class "Default")
      (node (ref "IC2") (pin "5") (pinfunction "SENSE_5") (pintype "passive"))
    )
    (net (code "132") (name "unconnected-(IC5-NC-Pad8)") (class "Default")
      (node (ref "IC5") (pin "8") (pinfunction "NC_8") (pintype "no_connect"))
    )
    (net (code "133") (name "unconnected-(IC5-REF-Pad1)") (class "Default")
      (node (ref "IC5") (pin "1") (pinfunction "REF_1") (pintype "passive"))
    )
    (net (code "134") (name "unconnected-(IC5-SENSE-Pad5)") (class "Default")
      (node (ref "IC5") (pin "5") (pinfunction "SENSE_5") (pintype "passive"))
    )
    (net (code "135") (name "unconnected-(IC6-NC-Pad8)") (class "Default")
      (node (ref "IC6") (pin "8") (pinfunction "NC_8") (pintype "no_connect"))
    )
    (net (code "136") (name "unconnected-(IC6-REF-Pad1)") (class "Default")
      (node (ref "IC6") (pin "1") (pinfunction "REF_1") (pintype "passive"))
    )
    (net (code "137") (name "unconnected-(IC6-SENSE-Pad5)") (class "Default")
      (node (ref "IC6") (pin "5") (pinfunction "SENSE_5") (pintype "passive"))
    )
    (net (code "138") (name "unconnected-(IC9-NC-Pad4)") (class "Default")
      (node (ref "IC9") (pin "4") (pinfunction "NC_4") (pintype "input"))
    )
    (net (code "139") (name "unconnected-(IC9-NC-Pad5)") (class "Default")
      (node (ref "IC9") (pin "5") (pinfunction "NC_5") (pintype "input"))
    )
    (net (code "140") (name "unconnected-(IC9-NC-Pad11)") (class "Default")
      (node (ref "IC9") (pin "11") (pinfunction "NC_11") (pintype "input"))
    )
    (net (code "141") (name "unconnected-(IC9-NC-Pad14)") (class "Default")
      (node (ref "IC9") (pin "14") (pinfunction "NC_14") (pintype "input"))
    )
    (net (code "142") (name "unconnected-(IC10-NC-Pad4)") (class "Default")
      (node (ref "IC10") (pin "4") (pinfunction "NC_4") (pintype "input"))
    )
    (net (code "143") (name "unconnected-(IC10-NC-Pad5)") (class "Default")
      (node (ref "IC10") (pin "5") (pinfunction "NC_5") (pintype "input"))
    )
    (net (code "144") (name "unconnected-(IC10-NC-Pad11)") (class "Default")
      (node (ref "IC10") (pin "11") (pinfunction "NC_11") (pintype "input"))
    )
    (net (code "145") (name "unconnected-(IC10-NC-Pad14)") (class "Default")
      (node (ref "IC10") (pin "14") (pinfunction "NC_14") (pintype "input"))
    )
    (net (code "146") (name "unconnected-(JP1-Pad6)") (class "Default")
      (node (ref "JP1") (pin "6") (pinfunction "6_6") (pintype "passive"))
    )
    (net (code "147") (name "unconnected-(U$1-CRSDV-PadP23)") (class "Default")
      (node (ref "U$1") (pin "P23") (pinfunction "CRSDV_P23") (pintype "bidirectional"))
    )
    (net (code "148") (name "unconnected-(U$1-DATA_RDY-PadP7)") (class "Default")
      (node (ref "U$1") (pin "P7") (pinfunction "DATA_RDY_P7") (pintype "bidirectional"))
    )
    (net (code "149") (name "unconnected-(U$1-DDM-PadP18)") (class "Default")
      (node (ref "U$1") (pin "P18") (pinfunction "DDM_P18") (pintype "bidirectional"))
    )
    (net (code "150") (name "unconnected-(U$1-DDP-PadP17)") (class "Default")
      (node (ref "U$1") (pin "P17") (pinfunction "DDP_P17") (pintype "bidirectional"))
    )
    (net (code "151") (name "unconnected-(U$1-EMDC-PadP26)") (class "Default")
      (node (ref "U$1") (pin "P26") (pinfunction "EMDC_P26") (pintype "bidirectional"))
    )
    (net (code "152") (name "unconnected-(U$1-EMDIO-PadP25)") (class "Default")
      (node (ref "U$1") (pin "P25") (pinfunction "EMDIO_P25") (pintype "bidirectional"))
    )
    (net (code "153") (name "unconnected-(U$1-ERX0-PadP30)") (class "Default")
      (node (ref "U$1") (pin "P30") (pinfunction "ERX0_P30") (pintype "bidirectional"))
    )
    (net (code "154") (name "unconnected-(U$1-ERX1-PadP28)") (class "Default")
      (node (ref "U$1") (pin "P28") (pinfunction "ERX1_P28") (pintype "bidirectional"))
    )
    (net (code "155") (name "unconnected-(U$1-ERXER-PadP24)") (class "Default")
      (node (ref "U$1") (pin "P24") (pinfunction "ERXER_P24") (pintype "bidirectional"))
    )
    (net (code "156") (name "unconnected-(U$1-ETX0-PadP29)") (class "Default")
      (node (ref "U$1") (pin "P29") (pinfunction "ETX0_P29") (pintype "bidirectional"))
    )
    (net (code "157") (name "unconnected-(U$1-ETX1-PadP27)") (class "Default")
      (node (ref "U$1") (pin "P27") (pinfunction "ETX1_P27") (pintype "bidirectional"))
    )
    (net (code "158") (name "unconnected-(U$1-ETX_EN-PadP21)") (class "Default")
      (node (ref "U$1") (pin "P21") (pinfunction "ETX_EN_P21") (pintype "bidirectional"))
    )
    (net (code "159") (name "unconnected-(U$1-GND2-PadP20)") (class "Default")
      (node (ref "U$1") (pin "P20") (pinfunction "GND2_P20") (pintype "bidirectional"))
    )
    (net (code "160") (name "unconnected-(U$1-NC-PadP19)") (class "Default")
      (node (ref "U$1") (pin "P19") (pinfunction "NC_P19") (pintype "bidirectional"))
    )
    (net (code "161") (name "unconnected-(U$1-READY-PadP16)") (class "Default")
      (node (ref "U$1") (pin "P16") (pinfunction "READY_P16") (pintype "bidirectional"))
    )
    (net (code "162") (name "unconnected-(U$1-RMII_RCLK-PadP22)") (class "Default")
      (node (ref "U$1") (pin "P22") (pinfunction "RMII_RCLK_P22") (pintype "bidirectional"))
    )
    (net (code "163") (name "unconnected-(U$1-SPI1_CLK-PadP12)") (class "Default")
      (node (ref "U$1") (pin "P12") (pinfunction "SPI1_CLK_P12") (pintype "bidirectional"))
    )
    (net (code "164") (name "unconnected-(U$1-SPI1_CS-PadP11)") (class "Default")
      (node (ref "U$1") (pin "P11") (pinfunction "SPI1_CS_P11") (pintype "bidirectional"))
    )
    (net (code "165") (name "unconnected-(U$1-SPI1_INT-PadP15)") (class "Default")
      (node (ref "U$1") (pin "P15") (pinfunction "SPI1_INT_P15") (pintype "bidirectional"))
    )
    (net (code "166") (name "unconnected-(U$1-SPI1_MISO-PadP13)") (class "Default")
      (node (ref "U$1") (pin "P13") (pinfunction "SPI1_MISO_P13") (pintype "bidirectional"))
    )
    (net (code "167") (name "unconnected-(U$1-SPI1_MOSI-PadP14)") (class "Default")
      (node (ref "U$1") (pin "P14") (pinfunction "SPI1_MOSI_P14") (pintype "bidirectional"))
    )
    (net (code "168") (name "unconnected-(U1-NRST-Pad69)") (class "Default")
      (node (ref "U1") (pin "69") (pinfunction "NRST_69") (pintype "bidirectional"))
    )
    (net (code "169") (name "unconnected-(U1-PA2-Pad85)") (class "Default")
      (node (ref "U1") (pin "85") (pinfunction "PA2_85") (pintype "bidirectional"))
    )
    (net (code "170") (name "unconnected-(U1-PA3-Pad84)") (class "Default")
      (node (ref "U1") (pin "84") (pinfunction "PA3_84") (pintype "bidirectional"))
    )
    (net (code "171") (name "unconnected-(U1-PA4-Pad83)") (class "Default")
      (node (ref "U1") (pin "83") (pinfunction "PA4_83") (pintype "bidirectional"))
    )
    (net (code "172") (name "unconnected-(U1-PA5-Pad25)") (class "Default")
      (node (ref "U1") (pin "25") (pinfunction "PA5_25") (pintype "bidirectional"))
    )
    (net (code "173") (name "unconnected-(U1-PA6-Pad82)") (class "Default")
      (node (ref "U1") (pin "82") (pinfunction "PA6_82") (pintype "bidirectional"))
    )
    (net (code "174") (name "unconnected-(U1-PA7-Pad26)") (class "Default")
      (node (ref "U1") (pin "26") (pinfunction "PA7_26") (pintype "bidirectional"))
    )
    (net (code "175") (name "unconnected-(U1-PA8-Pad27)") (class "Default")
      (node (ref "U1") (pin "27") (pinfunction "PA8_27") (pintype "bidirectional"))
    )
    (net (code "176") (name "unconnected-(U1-PA9-Pad2)") (class "Default")
      (node (ref "U1") (pin "2") (pinfunction "PA9_2") (pintype "bidirectional"))
    )
    (net (code "177") (name "unconnected-(U1-PA10-Pad3)") (class "Default")
      (node (ref "U1") (pin "3") (pinfunction "PA10_3") (pintype "bidirectional"))
    )
    (net (code "178") (name "unconnected-(U1-PA14-Pad7)") (class "Default")
      (node (ref "U1") (pin "7") (pinfunction "PA14_7") (pintype "bidirectional"))
    )
    (net (code "179") (name "unconnected-(U1-PA15-Pad8)") (class "Default")
      (node (ref "U1") (pin "8") (pinfunction "PA15_8") (pintype "bidirectional"))
    )
    (net (code "180") (name "unconnected-(U1-PA17-Pad9)") (class "Default")
      (node (ref "U1") (pin "9") (pinfunction "PA17_9") (pintype "bidirectional"))
    )
    (net (code "181") (name "unconnected-(U1-PA18-Pad70)") (class "Default")
      (node (ref "U1") (pin "70") (pinfunction "PA18_70") (pintype "bidirectional"))
    )
    (net (code "182") (name "unconnected-(U1-PA20-Pad72)") (class "Default")
      (node (ref "U1") (pin "72") (pinfunction "PA20_72") (pintype "bidirectional"))
    )
    (net (code "183") (name "unconnected-(U1-PA21-Pad107)") (class "Default")
      (node (ref "U1") (pin "107") (pinfunction "PA21_107") (pintype "bidirectional"))
    )
    (net (code "184") (name "unconnected-(U1-PA25-Pad108)") (class "Default")
      (node (ref "U1") (pin "108") (pinfunction "PA25_108") (pintype "bidirectional"))
    )
    (net (code "185") (name "unconnected-(U1-PA26-Pad109)") (class "Default")
      (node (ref "U1") (pin "109") (pinfunction "PA26_109") (pintype "bidirectional"))
    )
    (net (code "186") (name "unconnected-(U1-PA27-Pad110)") (class "Default")
      (node (ref "U1") (pin "110") (pinfunction "PA27_110") (pintype "bidirectional"))
    )
    (net (code "187") (name "unconnected-(U1-PA28-Pad111)") (class "Default")
      (node (ref "U1") (pin "111") (pinfunction "PA28_111") (pintype "bidirectional"))
    )
    (net (code "188") (name "unconnected-(U1-PA29-Pad112)") (class "Default")
      (node (ref "U1") (pin "112") (pinfunction "PA29_112") (pintype "bidirectional"))
    )
    (net (code "189") (name "unconnected-(U1-PB0-Pad113)") (class "Default")
      (node (ref "U1") (pin "113") (pinfunction "PB0_113") (pintype "bidirectional"))
    )
    (net (code "190") (name "unconnected-(U1-PB1-Pad114)") (class "Default")
      (node (ref "U1") (pin "114") (pinfunction "PB1_114") (pintype "bidirectional"))
    )
    (net (code "191") (name "unconnected-(U1-PB2-Pad115)") (class "Default")
      (node (ref "U1") (pin "115") (pinfunction "PB2_115") (pintype "bidirectional"))
    )
    (net (code "192") (name "unconnected-(U1-PB3-Pad118)") (class "Default")
      (node (ref "U1") (pin "118") (pinfunction "PB3_118") (pintype "bidirectional"))
    )
    (net (code "193") (name "unconnected-(U1-PB4-Pad119)") (class "Default")
      (node (ref "U1") (pin "119") (pinfunction "PB4_119") (pintype "bidirectional"))
    )
    (net (code "194") (name "unconnected-(U1-PB5-Pad120)") (class "Default")
      (node (ref "U1") (pin "120") (pinfunction "PB5_120") (pintype "bidirectional"))
    )
    (net (code "195") (name "unconnected-(U1-PB6-Pad121)") (class "Default")
      (node (ref "U1") (pin "121") (pinfunction "PB6_121") (pintype "bidirectional"))
    )
    (net (code "196") (name "unconnected-(U1-PB7-Pad122)") (class "Default")
      (node (ref "U1") (pin "122") (pinfunction "PB7_122") (pintype "bidirectional"))
    )
    (net (code "197") (name "unconnected-(U1-PB8-Pad123)") (class "Default")
      (node (ref "U1") (pin "123") (pinfunction "PB8_123") (pintype "bidirectional"))
    )
    (net (code "198") (name "unconnected-(U1-PB9-Pad127)") (class "Default")
      (node (ref "U1") (pin "127") (pinfunction "PB9_127") (pintype "bidirectional"))
    )
    (net (code "199") (name "unconnected-(U1-PB10-Pad128)") (class "Default")
      (node (ref "U1") (pin "128") (pinfunction "PB10_128") (pintype "bidirectional"))
    )
    (net (code "200") (name "unconnected-(U1-PB11-Pad129)") (class "Default")
      (node (ref "U1") (pin "129") (pinfunction "PB11_129") (pintype "bidirectional"))
    )
    (net (code "201") (name "unconnected-(U1-PB16-Pad77)") (class "Default")
      (node (ref "U1") (pin "77") (pinfunction "PB16_77") (pintype "bidirectional"))
    )
    (net (code "202") (name "unconnected-(U1-PB18-Pad89)") (class "Default")
      (node (ref "U1") (pin "89") (pinfunction "PB18_89") (pintype "bidirectional"))
    )
    (net (code "203") (name "unconnected-(U1-PB22-Pad141)") (class "Default")
      (node (ref "U1") (pin "141") (pinfunction "PB22_141") (pintype "bidirectional"))
    )
    (net (code "204") (name "unconnected-(U1-PB23-Pad142)") (class "Default")
      (node (ref "U1") (pin "142") (pinfunction "PB23_142") (pintype "bidirectional"))
    )
    (net (code "205") (name "unconnected-(U1-PB24-Pad143)") (class "Default")
      (node (ref "U1") (pin "143") (pinfunction "PB24_143") (pintype "bidirectional"))
    )
    (net (code "206") (name "unconnected-(U1-PB26-Pad1)") (class "Default")
      (node (ref "U1") (pin "1") (pinfunction "PB26_1") (pintype "bidirectional"))
    )
    (net (code "207") (name "unconnected-(U1-PB28-Pad28)") (class "Default")
      (node (ref "U1") (pin "28") (pinfunction "PB28_28") (pintype "bidirectional"))
    )
    (net (code "208") (name "unconnected-(U1-PB29-Pad29)") (class "Default")
      (node (ref "U1") (pin "29") (pinfunction "PB29_29") (pintype "bidirectional"))
    )
    (net (code "209") (name "unconnected-(U1-PB30-Pad30)") (class "Default")
      (node (ref "U1") (pin "30") (pinfunction "PB30_30") (pintype "bidirectional"))
    )
    (net (code "210") (name "unconnected-(U1-PB31-Pad31)") (class "Default")
      (node (ref "U1") (pin "31") (pinfunction "PB31_31") (pintype "bidirectional"))
    )
    (net (code "211") (name "unconnected-(U1-PC1-Pad55)") (class "Default")
      (node (ref "U1") (pin "55") (pinfunction "PC1_55") (pintype "bidirectional"))
    )
    (net (code "212") (name "unconnected-(U1-PC2-Pad59)") (class "Default")
      (node (ref "U1") (pin "59") (pinfunction "PC2_59") (pintype "bidirectional"))
    )
    (net (code "213") (name "unconnected-(U1-PC3-Pad60)") (class "Default")
      (node (ref "U1") (pin "60") (pinfunction "PC3_60") (pintype "bidirectional"))
    )
    (net (code "214") (name "unconnected-(U1-PC4-Pad116)") (class "Default")
      (node (ref "U1") (pin "116") (pinfunction "PC4_116") (pintype "bidirectional"))
    )
    (net (code "215") (name "unconnected-(U1-PC5-Pad63)") (class "Default")
      (node (ref "U1") (pin "63") (pinfunction "PC5_63") (pintype "bidirectional"))
    )
    (net (code "216") (name "unconnected-(U1-PC6-Pad64)") (class "Default")
      (node (ref "U1") (pin "64") (pinfunction "PC6_64") (pintype "bidirectional"))
    )
    (net (code "217") (name "unconnected-(U1-PC7-Pad65)") (class "Default")
      (node (ref "U1") (pin "65") (pinfunction "PC7_65") (pintype "bidirectional"))
    )
    (net (code "218") (name "unconnected-(U1-PC8-Pad66)") (class "Default")
      (node (ref "U1") (pin "66") (pinfunction "PC8_66") (pintype "bidirectional"))
    )
    (net (code "219") (name "unconnected-(U1-PC9-Pad67)") (class "Default")
      (node (ref "U1") (pin "67") (pinfunction "PC9_67") (pintype "bidirectional"))
    )
    (net (code "220") (name "unconnected-(U1-PC10-Pad117)") (class "Default")
      (node (ref "U1") (pin "117") (pinfunction "PC10_117") (pintype "bidirectional"))
    )
    (net (code "221") (name "unconnected-(U1-PC16-Pad98)") (class "Default")
      (node (ref "U1") (pin "98") (pinfunction "PC16_98") (pintype "bidirectional"))
    )
    (net (code "222") (name "unconnected-(U1-PC17-Pad99)") (class "Default")
      (node (ref "U1") (pin "99") (pinfunction "PC17_99") (pintype "bidirectional"))
    )
    (net (code "223") (name "unconnected-(U1-PC18-Pad100)") (class "Default")
      (node (ref "U1") (pin "100") (pinfunction "PC18_100") (pintype "bidirectional"))
    )
    (net (code "224") (name "unconnected-(U1-PC19-Pad101)") (class "Default")
      (node (ref "U1") (pin "101") (pinfunction "PC19_101") (pintype "bidirectional"))
    )
    (net (code "225") (name "unconnected-(U1-PC20-Pad131)") (class "Default")
      (node (ref "U1") (pin "131") (pinfunction "PC20_131") (pintype "bidirectional"))
    )
    (net (code "226") (name "unconnected-(U1-PC27-Pad138)") (class "Default")
      (node (ref "U1") (pin "138") (pinfunction "PC27_138") (pintype "bidirectional"))
    )
    (net (code "227") (name "unconnected-(U1-PC29-Pad102)") (class "Default")
      (node (ref "U1") (pin "102") (pinfunction "PC29_102") (pintype "bidirectional"))
    )
    (net (code "228") (name "unconnected-(U1-PC30-Pad103)") (class "Default")
      (node (ref "U1") (pin "103") (pinfunction "PC30_103") (pintype "bidirectional"))
    )
    (net (code "229") (name "unconnected-(U1-PD0-Pad13)") (class "Default")
      (node (ref "U1") (pin "13") (pinfunction "PD0_13") (pintype "bidirectional"))
    )
    (net (code "230") (name "unconnected-(U1-PD1-Pad14)") (class "Default")
      (node (ref "U1") (pin "14") (pinfunction "PD1_14") (pintype "bidirectional"))
    )
    (net (code "231") (name "unconnected-(U1-PD2-Pad15)") (class "Default")
      (node (ref "U1") (pin "15") (pinfunction "PD2_15") (pintype "bidirectional"))
    )
    (net (code "232") (name "unconnected-(U1-PD3-Pad16)") (class "Default")
      (node (ref "U1") (pin "16") (pinfunction "PD3_16") (pintype "bidirectional"))
    )
    (net (code "233") (name "unconnected-(U1-PD4-Pad17)") (class "Default")
      (node (ref "U1") (pin "17") (pinfunction "PD4_17") (pintype "bidirectional"))
    )
    (net (code "234") (name "unconnected-(U1-PD5-Pad18)") (class "Default")
      (node (ref "U1") (pin "18") (pinfunction "PD5_18") (pintype "bidirectional"))
    )
    (net (code "235") (name "unconnected-(U1-PD6-Pad19)") (class "Default")
      (node (ref "U1") (pin "19") (pinfunction "PD6_19") (pintype "bidirectional"))
    )
    (net (code "236") (name "unconnected-(U1-PD7-Pad20)") (class "Default")
      (node (ref "U1") (pin "20") (pinfunction "PD7_20") (pintype "bidirectional"))
    )
    (net (code "237") (name "unconnected-(U1-PD8-Pad21)") (class "Default")
      (node (ref "U1") (pin "21") (pinfunction "PD8_21") (pintype "bidirectional"))
    )
    (net (code "238") (name "unconnected-(U1-PD9-Pad22)") (class "Default")
      (node (ref "U1") (pin "22") (pinfunction "PD9_22") (pintype "bidirectional"))
    )
    (net (code "239") (name "unconnected-(U1-PD10-Pad32)") (class "Default")
      (node (ref "U1") (pin "32") (pinfunction "PD10_32") (pintype "bidirectional"))
    )
    (net (code "240") (name "unconnected-(U1-SHDN-Pad50)") (class "Default")
      (node (ref "U1") (pin "50") (pinfunction "SHDN_50") (pintype "output"))
    )
    (net (code "241") (name "unconnected-(U1-TST-Pad51)") (class "Default")
      (node (ref "U1") (pin "51") (pinfunction "TST_51") (pintype "input"))
    )
    (net (code "242") (name "unconnected-(U7-WC-PadPIN7)") (class "Default")
      (node (ref "U7") (pin "PIN7") (pinfunction "WC_PIN7") (pintype "bidirectional"))
    )
    (net (code "243") (name "unconnected-(X1-PadS1)") (class "Default")
      (node (ref "X1") (pin "S1") (pinfunction "S1_S1") (pintype "passive"))
    )
    (net (code "244") (name "unconnected-(X1-PadS2)") (class "Default")
      (node (ref "X1") (pin "S2") (pinfunction "S2_S2") (pintype "passive"))
    )
  )
)
